# Mainboard_v1_1.net
KiCad netlist of a schematic drawn in Altium Designer
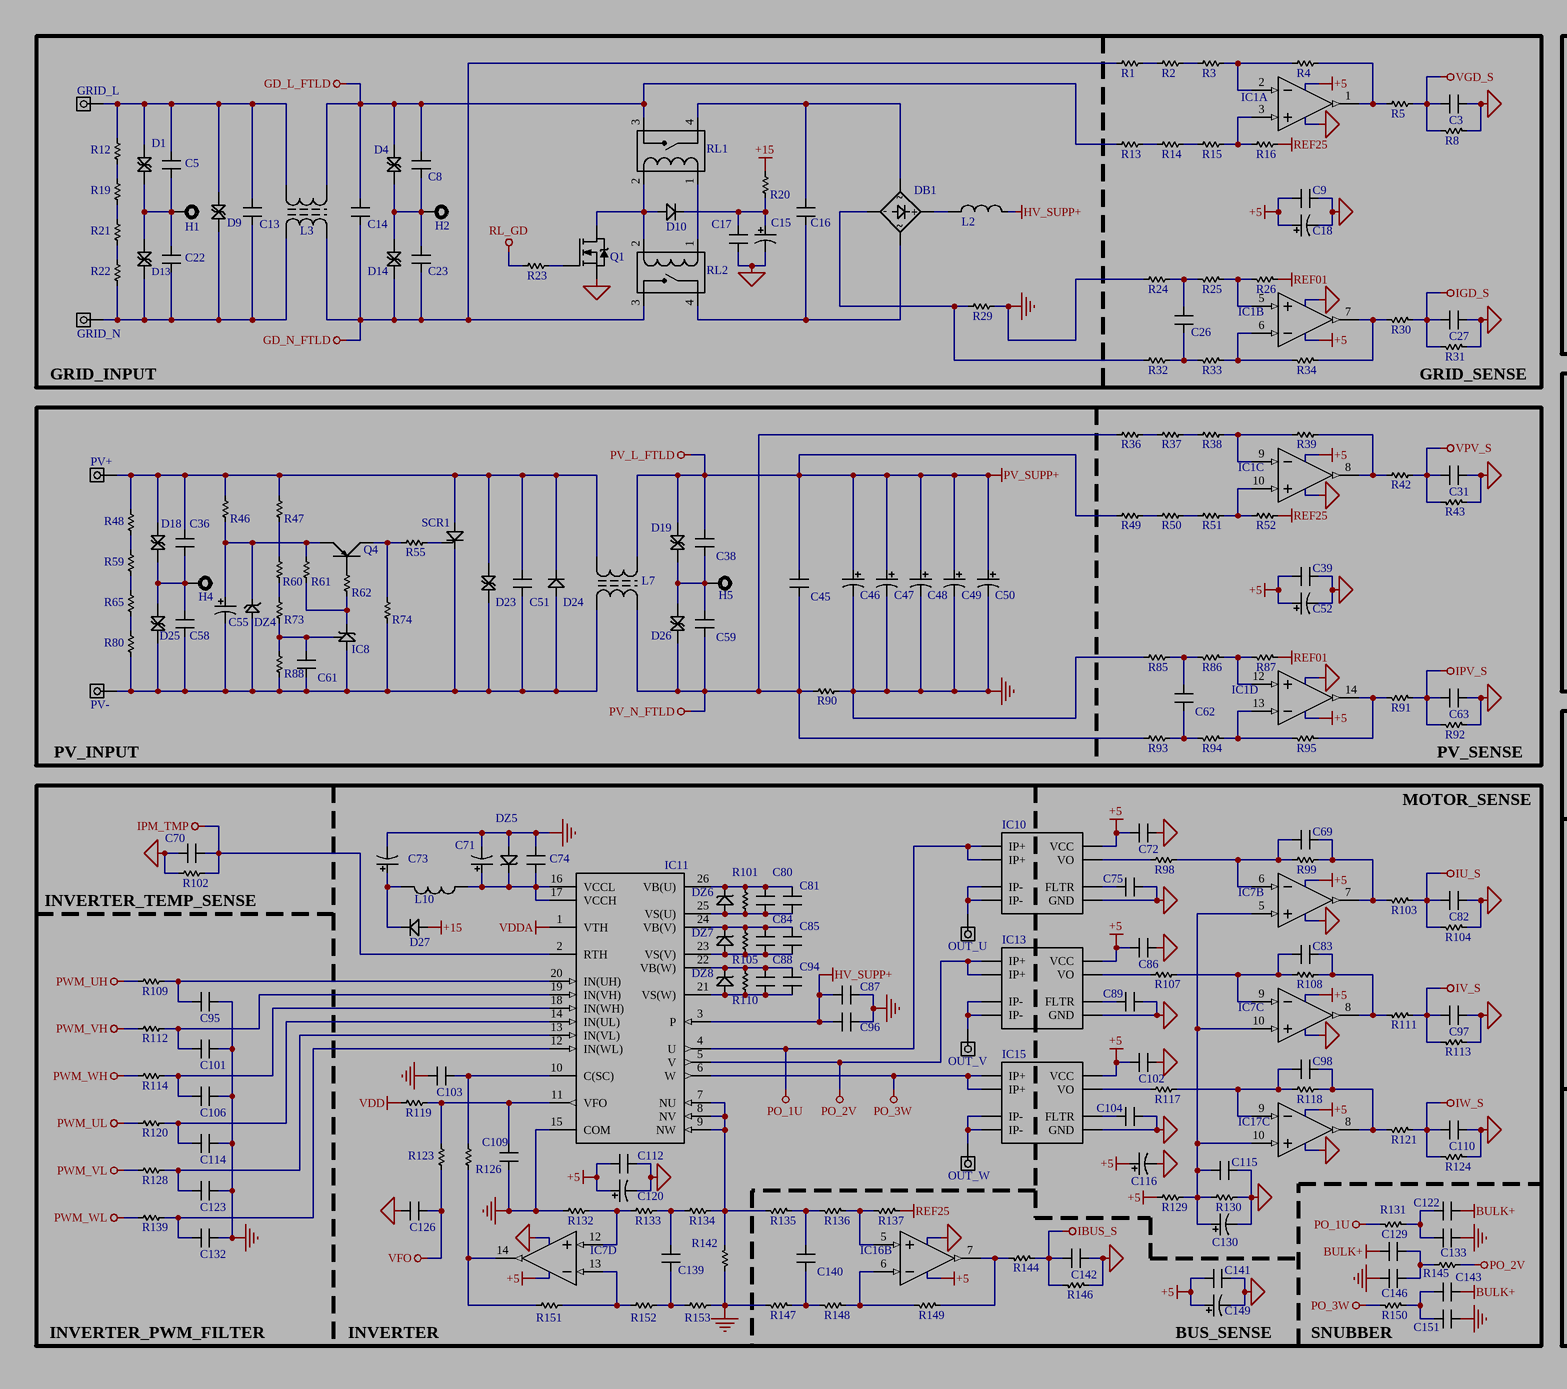
[diagram p0: Mainboard_v1_1.SchDoc, left]
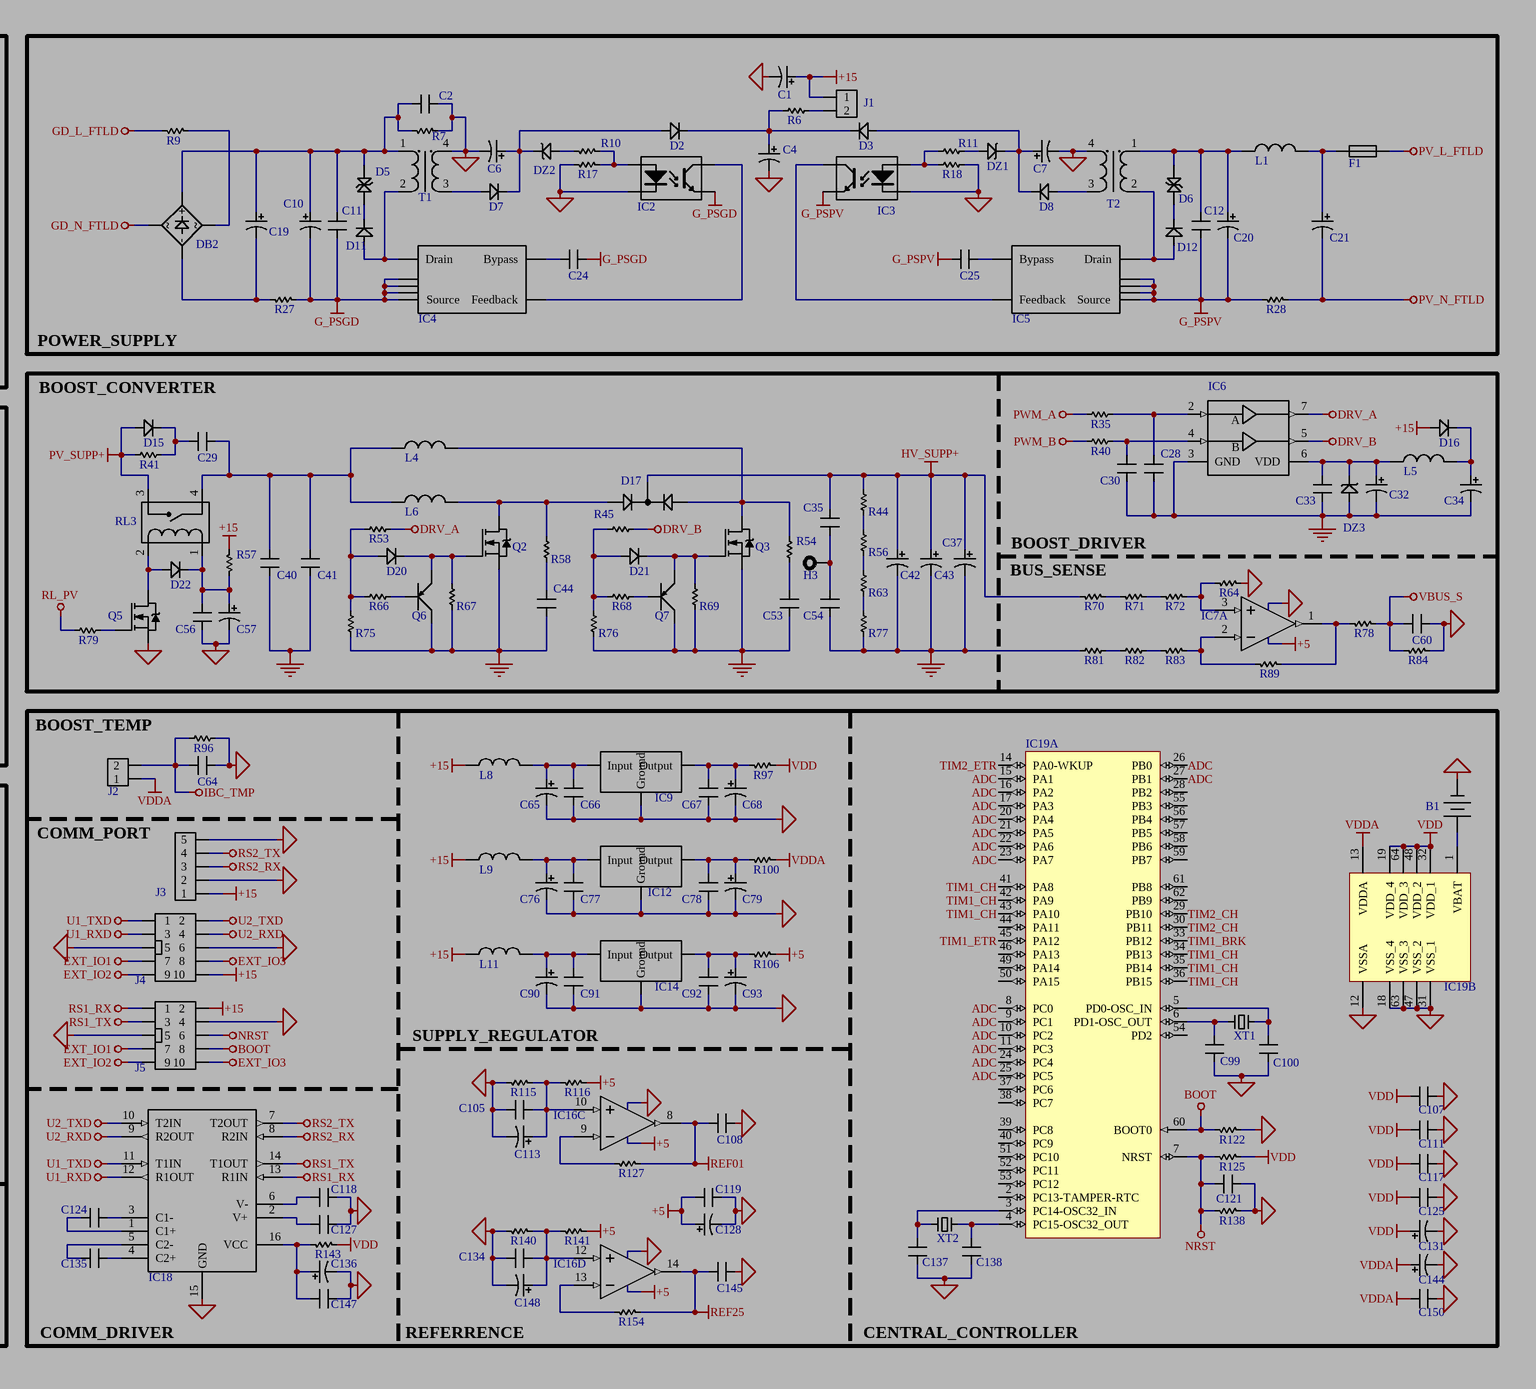
[diagram p1: Mainboard_v1_1.SchDoc, right]

(export (version "E")
  (design (tool "Eeschema 10.0.6"))
  (components
    (comp (ref "B1") (value "BATTERY") (libsource (lib "MeoLib_v2") (part "BATTERY")))
    (comp (ref "C1") (value "CAP-POL") (footprint "CAP-ELECT-5") (libsource (lib "") (part "CAP-POL_1")))
    (comp (ref "C2") (value "104") (footprint "CAP20") (libsource (lib "MeoLib_v2") (part "CAP")))
    (comp (ref "C3") (value "104") (footprint "CAP20") (libsource (lib "MeoLib_v2") (part "CAP")))
    (comp (ref "C4") (value "CAP-POL") (footprint "CAP-ELECT-5") (libsource (lib "") (part "CAP-POL_1")))
    (comp (ref "C5") (value "104") (footprint "CAP20") (libsource (lib "MeoLib_v2") (part "CAP")))
    (comp (ref "C6") (value "CAP-POL") (footprint "CAP-ELECT-5") (libsource (lib "") (part "CAP-POL_1")))
    (comp (ref "C7")
      (value "CAP-POL")
      (footprint "CAP-ELECT-5")
      (libsource (lib "MeoLib_v2") (part "CAP-POL"))
    )
    (comp (ref "C8") (value "104") (footprint "CAP20") (libsource (lib "MeoLib_v2") (part "CAP")))
    (comp (ref "C9") (value "104") (footprint "CAP20") (libsource (lib "MeoLib_v2") (part "CAP")))
    (comp (ref "C10")
      (value "CAP-POL")
      (footprint "CAP-ELECT-5")
      (libsource (lib "MeoLib_v2") (part "CAP-POL"))
    )
    (comp (ref "C11") (value "104") (footprint "CAP20") (libsource (lib "MeoLib_v2") (part "CAP")))
    (comp (ref "C12") (value "104") (footprint "CAP20") (libsource (lib "MeoLib_v2") (part "CAP")))
    (comp (ref "C13") (value "104") (footprint "CAP20") (libsource (lib "MeoLib_v2") (part "CAP")))
    (comp (ref "C14") (value "104") (footprint "CAP20") (libsource (lib "MeoLib_v2") (part "CAP")))
    (comp (ref "C15")
      (value "CAP-POL")
      (footprint "CAP-ELECT-5")
      (libsource (lib "MeoLib_v2") (part "CAP-POL"))
    )
    (comp (ref "C16") (value "NULL") (footprint "CAP20") (libsource (lib "MeoLib_v2") (part "CAP")))
    (comp (ref "C17") (value "CAP") (footprint "CAP20") (libsource (lib "MeoLib_v2") (part "CAP")))
    (comp (ref "C18")
      (value "CAP-POL")
      (footprint "CAP-ELECT-5")
      (libsource (lib "MeoLib_v2") (part "CAP-POL"))
    )
    (comp (ref "C19") (value "CAP-POL") (footprint "CAP-ELECT-5") (libsource (lib "") (part "CAP-POL_1")))
    (comp (ref "C20") (value "CAP-POL") (footprint "CAP-ELECT-5") (libsource (lib "") (part "CAP-POL_1")))
    (comp (ref "C21") (value "CAP-POL") (footprint "CAP-ELECT-5") (libsource (lib "") (part "CAP-POL_1")))
    (comp (ref "C22") (value "104") (footprint "CAP20") (libsource (lib "MeoLib_v2") (part "CAP")))
    (comp (ref "C23") (value "104") (footprint "CAP20") (libsource (lib "MeoLib_v2") (part "CAP")))
    (comp (ref "C24") (value "104") (footprint "CAP20") (libsource (lib "MeoLib_v2") (part "CAP")))
    (comp (ref "C25") (value "104") (footprint "CAP20") (libsource (lib "MeoLib_v2") (part "CAP")))
    (comp (ref "C26") (value "104") (footprint "CAP20") (libsource (lib "MeoLib_v2") (part "CAP")))
    (comp (ref "C27") (value "104") (footprint "CAP20") (libsource (lib "MeoLib_v2") (part "CAP")))
    (comp (ref "C28") (value "104") (footprint "CAP20") (libsource (lib "MeoLib_v2") (part "CAP")))
    (comp (ref "C29") (value "104") (footprint "CAP20") (libsource (lib "MeoLib_v2") (part "CAP")))
    (comp (ref "C30") (value "104") (footprint "CAP20") (libsource (lib "MeoLib_v2") (part "CAP")))
    (comp (ref "C31") (value "104") (footprint "CAP20") (libsource (lib "MeoLib_v2") (part "CAP")))
    (comp (ref "C32") (value "CAP-POL") (footprint "CAP-ELECT-5") (libsource (lib "") (part "CAP-POL_1")))
    (comp (ref "C33") (value "104") (footprint "CAP20") (libsource (lib "MeoLib_v2") (part "CAP")))
    (comp (ref "C34") (value "CAP-POL") (footprint "CAP-ELECT-5") (libsource (lib "") (part "CAP-POL_1")))
    (comp (ref "C35") (value "104") (footprint "CAP20") (libsource (lib "MeoLib_v2") (part "CAP")))
    (comp (ref "C36") (value "104") (footprint "CAP20") (libsource (lib "MeoLib_v2") (part "CAP")))
    (comp (ref "C37") (value "CAP-POL") (footprint "CAP-ELECT-5") (libsource (lib "") (part "CAP-POL_1")))
    (comp (ref "C38") (value "104") (footprint "CAP20") (libsource (lib "MeoLib_v2") (part "CAP")))
    (comp (ref "C39") (value "104") (footprint "CAP20") (libsource (lib "MeoLib_v2") (part "CAP")))
    (comp (ref "C40") (value "104") (footprint "CAP20") (libsource (lib "MeoLib_v2") (part "CAP")))
    (comp (ref "C41") (value "104") (footprint "CAP20") (libsource (lib "MeoLib_v2") (part "CAP")))
    (comp (ref "C42") (value "CAP-POL") (footprint "CAP-ELECT-5") (libsource (lib "") (part "CAP-POL_1")))
    (comp (ref "C43") (value "CAP-POL") (footprint "CAP-ELECT-5") (libsource (lib "") (part "CAP-POL_1")))
    (comp (ref "C44") (value "104") (footprint "CAP20") (libsource (lib "MeoLib_v2") (part "CAP")))
    (comp (ref "C45") (value "104") (footprint "CAP20") (libsource (lib "MeoLib_v2") (part "CAP")))
    (comp (ref "C46") (value "CAP-POL") (footprint "CAP-ELECT-5") (libsource (lib "") (part "CAP-POL_1")))
    (comp (ref "C47") (value "CAP-POL") (footprint "CAP-ELECT-5") (libsource (lib "") (part "CAP-POL_1")))
    (comp (ref "C48") (value "CAP-POL") (footprint "CAP-ELECT-5") (libsource (lib "") (part "CAP-POL_1")))
    (comp (ref "C49") (value "CAP-POL") (footprint "CAP-ELECT-5") (libsource (lib "") (part "CAP-POL_1")))
    (comp (ref "C50") (value "CAP-POL") (footprint "CAP-ELECT-5") (libsource (lib "") (part "CAP-POL_1")))
    (comp (ref "C51") (value "104") (footprint "CAP20") (libsource (lib "MeoLib_v2") (part "CAP")))
    (comp (ref "C52")
      (value "CAP-POL")
      (footprint "CAP-ELECT-5")
      (libsource (lib "MeoLib_v2") (part "CAP-POL"))
    )
    (comp (ref "C53") (value "104") (footprint "CAP20") (libsource (lib "MeoLib_v2") (part "CAP")))
    (comp (ref "C54") (value "104") (footprint "CAP20") (libsource (lib "MeoLib_v2") (part "CAP")))
    (comp (ref "C55")
      (value "CAP-POL")
      (footprint "CAP-ELECT-5")
      (libsource (lib "MeoLib_v2") (part "CAP-POL"))
    )
    (comp (ref "C56") (value "104") (footprint "CAP20") (libsource (lib "MeoLib_v2") (part "CAP")))
    (comp (ref "C57") (value "CAP-POL") (footprint "CAP-ELECT-5") (libsource (lib "") (part "CAP-POL_1")))
    (comp (ref "C58") (value "104") (footprint "CAP20") (libsource (lib "MeoLib_v2") (part "CAP")))
    (comp (ref "C59") (value "104") (footprint "CAP20") (libsource (lib "MeoLib_v2") (part "CAP")))
    (comp (ref "C60") (value "104") (footprint "CAP20") (libsource (lib "MeoLib_v2") (part "CAP")))
    (comp (ref "C61") (value "104") (footprint "CAP20") (libsource (lib "MeoLib_v2") (part "CAP")))
    (comp (ref "C62") (value "104") (footprint "CAP20") (libsource (lib "MeoLib_v2") (part "CAP")))
    (comp (ref "C63") (value "104") (footprint "CAP20") (libsource (lib "MeoLib_v2") (part "CAP")))
    (comp (ref "C64") (value "104") (footprint "CAP20") (libsource (lib "MeoLib_v2") (part "CAP")))
    (comp (ref "C65") (value "CAP-POL") (footprint "CAP-ELECT-5") (libsource (lib "") (part "CAP-POL_1")))
    (comp (ref "C66") (value "CAP") (footprint "CAP20") (libsource (lib "MeoLib_v2") (part "CAP")))
    (comp (ref "C67") (value "CAP") (footprint "CAP20") (libsource (lib "MeoLib_v2") (part "CAP")))
    (comp (ref "C68")
      (value "CAP-POL")
      (footprint "CAP-ELECT-5")
      (libsource (lib "MeoLib_v2") (part "CAP-POL"))
    )
    (comp (ref "C69") (value "104") (footprint "CAP20") (libsource (lib "MeoLib_v2") (part "CAP")))
    (comp (ref "C70") (value "104") (footprint "CAP20") (libsource (lib "MeoLib_v2") (part "CAP")))
    (comp (ref "C71") (value "CAP-POL") (footprint "CAP-ELECT-5") (libsource (lib "") (part "CAP-POL_1")))
    (comp (ref "C72") (value "104") (footprint "CAP20") (libsource (lib "MeoLib_v2") (part "CAP")))
    (comp (ref "C73") (value "CAP-POL") (footprint "CAP-ELECT-5") (libsource (lib "") (part "CAP-POL_1")))
    (comp (ref "C74") (value "104") (footprint "CAP20") (libsource (lib "MeoLib_v2") (part "CAP")))
    (comp (ref "C75") (value "104") (footprint "CAP20") (libsource (lib "MeoLib_v2") (part "CAP")))
    (comp (ref "C76") (value "CAP-POL") (footprint "CAP-ELECT-5") (libsource (lib "") (part "CAP-POL_1")))
    (comp (ref "C77") (value "CAP") (footprint "CAP20") (libsource (lib "MeoLib_v2") (part "CAP")))
    (comp (ref "C78") (value "CAP") (footprint "CAP20") (libsource (lib "MeoLib_v2") (part "CAP")))
    (comp (ref "C79")
      (value "CAP-POL")
      (footprint "CAP-ELECT-5")
      (libsource (lib "MeoLib_v2") (part "CAP-POL"))
    )
    (comp (ref "C80") (value "104") (footprint "CAP20") (libsource (lib "MeoLib_v2") (part "CAP")))
    (comp (ref "C81") (value "104") (footprint "CAP20") (libsource (lib "MeoLib_v2") (part "CAP")))
    (comp (ref "C82") (value "104") (footprint "CAP20") (libsource (lib "MeoLib_v2") (part "CAP")))
    (comp (ref "C83") (value "104") (footprint "CAP20") (libsource (lib "MeoLib_v2") (part "CAP")))
    (comp (ref "C84") (value "104") (footprint "CAP20") (libsource (lib "MeoLib_v2") (part "CAP")))
    (comp (ref "C85") (value "104") (footprint "CAP20") (libsource (lib "MeoLib_v2") (part "CAP")))
    (comp (ref "C86") (value "104") (footprint "CAP20") (libsource (lib "MeoLib_v2") (part "CAP")))
    (comp (ref "C87") (value "104") (footprint "CAP20") (libsource (lib "MeoLib_v2") (part "CAP")))
    (comp (ref "C88") (value "104") (footprint "CAP20") (libsource (lib "MeoLib_v2") (part "CAP")))
    (comp (ref "C89") (value "104") (footprint "CAP20") (libsource (lib "MeoLib_v2") (part "CAP")))
    (comp (ref "C90") (value "CAP-POL") (footprint "CAP-ELECT-5") (libsource (lib "") (part "CAP-POL_1")))
    (comp (ref "C91") (value "CAP") (footprint "CAP20") (libsource (lib "MeoLib_v2") (part "CAP")))
    (comp (ref "C92") (value "CAP") (footprint "CAP20") (libsource (lib "MeoLib_v2") (part "CAP")))
    (comp (ref "C93")
      (value "CAP-POL")
      (footprint "CAP-ELECT-5")
      (libsource (lib "MeoLib_v2") (part "CAP-POL"))
    )
    (comp (ref "C94") (value "104") (footprint "CAP20") (libsource (lib "MeoLib_v2") (part "CAP")))
    (comp (ref "C95") (value "104") (footprint "CAP20") (libsource (lib "MeoLib_v2") (part "CAP")))
    (comp (ref "C96") (value "104") (footprint "CAP20") (libsource (lib "MeoLib_v2") (part "CAP")))
    (comp (ref "C97") (value "104") (footprint "CAP20") (libsource (lib "MeoLib_v2") (part "CAP")))
    (comp (ref "C98") (value "104") (footprint "CAP20") (libsource (lib "MeoLib_v2") (part "CAP")))
    (comp (ref "C99") (value "CAP") (footprint "CAP20") (libsource (lib "MeoLib_v2") (part "CAP")))
    (comp (ref "C100") (value "CAP") (footprint "CAP20") (libsource (lib "MeoLib_v2") (part "CAP")))
    (comp (ref "C101") (value "104") (footprint "CAP20") (libsource (lib "MeoLib_v2") (part "CAP")))
    (comp (ref "C102") (value "104") (footprint "CAP20") (libsource (lib "MeoLib_v2") (part "CAP")))
    (comp (ref "C103") (value "104") (footprint "CAP20") (libsource (lib "MeoLib_v2") (part "CAP")))
    (comp (ref "C104") (value "104") (footprint "CAP20") (libsource (lib "MeoLib_v2") (part "CAP")))
    (comp (ref "C105") (value "104") (footprint "CAP20") (libsource (lib "MeoLib_v2") (part "CAP")))
    (comp (ref "C106") (value "104") (footprint "CAP20") (libsource (lib "MeoLib_v2") (part "CAP")))
    (comp (ref "C107") (value "CAP") (footprint "CAP20") (libsource (lib "MeoLib_v2") (part "CAP")))
    (comp (ref "C108") (value "104") (footprint "CAP20") (libsource (lib "MeoLib_v2") (part "CAP")))
    (comp (ref "C109") (value "104") (footprint "CAP20") (libsource (lib "MeoLib_v2") (part "CAP")))
    (comp (ref "C110") (value "104") (footprint "CAP20") (libsource (lib "MeoLib_v2") (part "CAP")))
    (comp (ref "C111") (value "CAP") (footprint "CAP20") (libsource (lib "MeoLib_v2") (part "CAP")))
    (comp (ref "C112") (value "104") (footprint "CAP20") (libsource (lib "MeoLib_v2") (part "CAP")))
    (comp (ref "C113") (value "CAP-POL") (footprint "CAP-ELECT-5") (libsource (lib "") (part "CAP-POL_1")))
    (comp (ref "C114") (value "104") (footprint "CAP20") (libsource (lib "MeoLib_v2") (part "CAP")))
    (comp (ref "C115") (value "104") (footprint "CAP20") (libsource (lib "MeoLib_v2") (part "CAP")))
    (comp (ref "C116")
      (value "CAP-POL")
      (footprint "CAP-ELECT-5")
      (libsource (lib "MeoLib_v2") (part "CAP-POL"))
    )
    (comp (ref "C117") (value "CAP") (footprint "CAP20") (libsource (lib "MeoLib_v2") (part "CAP")))
    (comp (ref "C118") (value "CAP") (footprint "CAP20") (libsource (lib "MeoLib_v2") (part "CAP")))
    (comp (ref "C119") (value "104") (footprint "CAP20") (libsource (lib "MeoLib_v2") (part "CAP")))
    (comp (ref "C120")
      (value "CAP-POL")
      (footprint "CAP-ELECT-5")
      (libsource (lib "MeoLib_v2") (part "CAP-POL"))
    )
    (comp (ref "C121") (value "104") (footprint "CAP20") (libsource (lib "MeoLib_v2") (part "CAP")))
    (comp (ref "C122") (value "104") (footprint "CAP20") (libsource (lib "MeoLib_v2") (part "CAP")))
    (comp (ref "C123") (value "104") (footprint "CAP20") (libsource (lib "MeoLib_v2") (part "CAP")))
    (comp (ref "C124") (value "CAP") (footprint "CAP20") (libsource (lib "MeoLib_v2") (part "CAP")))
    (comp (ref "C125") (value "CAP") (footprint "CAP20") (libsource (lib "MeoLib_v2") (part "CAP")))
    (comp (ref "C126") (value "104") (footprint "CAP20") (libsource (lib "MeoLib_v2") (part "CAP")))
    (comp (ref "C127") (value "CAP") (footprint "CAP20") (libsource (lib "MeoLib_v2") (part "CAP")))
    (comp (ref "C128")
      (value "CAP-POL")
      (footprint "CAP-ELECT-5")
      (libsource (lib "MeoLib_v2") (part "CAP-POL"))
    )
    (comp (ref "C129") (value "104") (footprint "CAP20") (libsource (lib "MeoLib_v2") (part "CAP")))
    (comp (ref "C130")
      (value "CAP-POL")
      (footprint "CAP-ELECT-5")
      (libsource (lib "MeoLib_v2") (part "CAP-POL"))
    )
    (comp (ref "C131")
      (value "CAP-POL")
      (footprint "CAP-ELECT-5")
      (libsource (lib "MeoLib_v2") (part "CAP-POL"))
    )
    (comp (ref "C132") (value "104") (footprint "CAP20") (libsource (lib "MeoLib_v2") (part "CAP")))
    (comp (ref "C133") (value "104") (footprint "CAP20") (libsource (lib "MeoLib_v2") (part "CAP")))
    (comp (ref "C134") (value "104") (footprint "CAP20") (libsource (lib "MeoLib_v2") (part "CAP")))
    (comp (ref "C135") (value "CAP") (footprint "CAP20") (libsource (lib "MeoLib_v2") (part "CAP")))
    (comp (ref "C136")
      (value "CAP-POL")
      (footprint "CAP-ELECT-5")
      (libsource (lib "MeoLib_v2") (part "CAP-POL"))
    )
    (comp (ref "C137") (value "CAP") (footprint "CAP20") (libsource (lib "MeoLib_v2") (part "CAP")))
    (comp (ref "C138") (value "CAP") (footprint "CAP20") (libsource (lib "MeoLib_v2") (part "CAP")))
    (comp (ref "C139") (value "104") (footprint "CAP20") (libsource (lib "MeoLib_v2") (part "CAP")))
    (comp (ref "C140") (value "104") (footprint "CAP20") (libsource (lib "MeoLib_v2") (part "CAP")))
    (comp (ref "C141") (value "104") (footprint "CAP20") (libsource (lib "MeoLib_v2") (part "CAP")))
    (comp (ref "C142") (value "104") (footprint "CAP20") (libsource (lib "MeoLib_v2") (part "CAP")))
    (comp (ref "C143") (value "104") (footprint "CAP20") (libsource (lib "MeoLib_v2") (part "CAP")))
    (comp (ref "C144")
      (value "CAP-POL")
      (footprint "CAP-ELECT-5")
      (libsource (lib "MeoLib_v2") (part "CAP-POL"))
    )
    (comp (ref "C145") (value "104") (footprint "CAP20") (libsource (lib "MeoLib_v2") (part "CAP")))
    (comp (ref "C146") (value "104") (footprint "CAP20") (libsource (lib "MeoLib_v2") (part "CAP")))
    (comp (ref "C147") (value "CAP") (footprint "CAP20") (libsource (lib "MeoLib_v2") (part "CAP")))
    (comp (ref "C148") (value "CAP-POL") (footprint "CAP-ELECT-5") (libsource (lib "") (part "CAP-POL_1")))
    (comp (ref "C149")
      (value "CAP-POL")
      (footprint "CAP-ELECT-5")
      (libsource (lib "MeoLib_v2") (part "CAP-POL"))
    )
    (comp (ref "C150") (value "CAP") (footprint "CAP20") (libsource (lib "MeoLib_v2") (part "CAP")))
    (comp (ref "C151") (value "104") (footprint "CAP20") (libsource (lib "MeoLib_v2") (part "CAP")))
    (comp (ref "D1") (value "DB3") (footprint "DIA_DB3") (libsource (lib "MeoLib_v2") (part "DB3")))
    (comp (ref "D2")
      (value "Diode")
      (footprint "DIO_DO41")
      (fields (field (name "PUBLISHER") "Altium Limited"))
      (libsource (lib "MeoLib_v2") (part "Diode"))
    )
    (comp (ref "D3")
      (value "Diode")
      (footprint "DIO_DO41")
      (fields (field (name "PUBLISHER") "Altium Limited"))
      (libsource (lib "MeoLib_v2") (part "Diode"))
    )
    (comp (ref "D4") (value "DB3") (footprint "DIA_DB3") (libsource (lib "MeoLib_v2") (part "DB3")))
    (comp (ref "D5")
      (value "Diode TVS")
      (footprint "DIO_DO15-TVS")
      (libsource (lib "MeoLib_v2") (part "Diode TVS"))
    )
    (comp (ref "D6")
      (value "Diode TVS")
      (footprint "DIO_DO15-TVS")
      (libsource (lib "MeoLib_v2") (part "Diode TVS"))
    )
    (comp (ref "D7")
      (value "Diode")
      (footprint "DIO_DO41")
      (fields (field (name "PUBLISHER") "Altium Limited"))
      (libsource (lib "MeoLib_v2") (part "Diode"))
    )
    (comp (ref "D8")
      (value "Diode")
      (footprint "DIO_DO41")
      (fields (field (name "PUBLISHER") "Altium Limited"))
      (libsource (lib "MeoLib_v2") (part "Diode"))
    )
    (comp (ref "D9") (value "DB3") (footprint "DIA_DB3") (libsource (lib "MeoLib_v2") (part "DB3")))
    (comp (ref "D10")
      (value "Diode")
      (footprint "DIO_DO41")
      (fields (field (name "PUBLISHER") "Altium Limited"))
      (libsource (lib "MeoLib_v2") (part "Diode"))
    )
    (comp (ref "D11")
      (value "Diode")
      (footprint "DIO_DO41")
      (fields (field (name "PUBLISHER") "Altium Limited"))
      (libsource (lib "MeoLib_v2") (part "Diode"))
    )
    (comp (ref "D12")
      (value "Diode")
      (footprint "DIO_DO41")
      (fields (field (name "PUBLISHER") "Altium Limited"))
      (libsource (lib "MeoLib_v2") (part "Diode"))
    )
    (comp (ref "D13") (value "DB3") (footprint "DIA_DB3") (libsource (lib "MeoLib_v2") (part "DB3")))
    (comp (ref "D14") (value "DB3") (footprint "DIA_DB3") (libsource (lib "MeoLib_v2") (part "DB3")))
    (comp (ref "D15")
      (value "Diode")
      (footprint "DIO_DO41")
      (fields (field (name "PUBLISHER") "Altium Limited"))
      (libsource (lib "MeoLib_v2") (part "Diode"))
    )
    (comp (ref "D16")
      (value "Diode")
      (footprint "DIO_DO41")
      (fields (field (name "PUBLISHER") "Altium Limited"))
      (libsource (lib "MeoLib_v2") (part "Diode"))
    )
    (comp (ref "D17")
      (value "Diode Dual")
      (footprint "TO-220")
      (libsource (lib "MeoLib_v2") (part "Diode Dual"))
    )
    (comp (ref "D18") (value "DB3") (footprint "DIA_DB3") (libsource (lib "MeoLib_v2") (part "DB3")))
    (comp (ref "D19") (value "DB3") (footprint "DIA_DB3") (libsource (lib "MeoLib_v2") (part "DB3")))
    (comp (ref "D20")
      (value "Diode")
      (footprint "DIO_DO41")
      (fields (field (name "PUBLISHER") "Altium Limited"))
      (libsource (lib "MeoLib_v2") (part "Diode"))
    )
    (comp (ref "D21")
      (value "Diode")
      (footprint "DIO_DO41")
      (fields (field (name "PUBLISHER") "Altium Limited"))
      (libsource (lib "MeoLib_v2") (part "Diode"))
    )
    (comp (ref "D22")
      (value "Diode")
      (footprint "DIO_DO41")
      (fields (field (name "PUBLISHER") "Altium Limited"))
      (libsource (lib "MeoLib_v2") (part "Diode"))
    )
    (comp (ref "D23") (value "DB3") (footprint "DIA_DB3") (libsource (lib "MeoLib_v2") (part "DB3")))
    (comp (ref "D24")
      (value "Diode")
      (footprint "DIO_DO41")
      (fields (field (name "PUBLISHER") "Altium Limited"))
      (libsource (lib "MeoLib_v2") (part "Diode"))
    )
    (comp (ref "D25") (value "DB3") (footprint "DIA_DB3") (libsource (lib "MeoLib_v2") (part "DB3")))
    (comp (ref "D26") (value "DB3") (footprint "DIA_DB3") (libsource (lib "MeoLib_v2") (part "DB3")))
    (comp (ref "D27")
      (value "Diode")
      (footprint "DIO_DO41")
      (fields (field (name "PUBLISHER") "Altium Limited"))
      (libsource (lib "MeoLib_v2") (part "Diode"))
    )
    (comp (ref "DB1")
      (value "Diode Bridge")
      (footprint "DB25A")
      (libsource (lib "MeoLib_v2") (part "Diode Bridge"))
    )
    (comp (ref "DB2")
      (value "Diode Bridge")
      (footprint "DB25A")
      (libsource (lib "MeoLib_v2") (part "Diode Bridge"))
    )
    (comp (ref "DZ1")
      (value "Diode Zener")
      (footprint "DIO_DZ1W")
      (libsource (lib "MeoLib_v2") (part "Diode Zener"))
    )
    (comp (ref "DZ2")
      (value "Diode Zener")
      (footprint "DIO_DZ1W")
      (libsource (lib "MeoLib_v2") (part "Diode Zener"))
    )
    (comp (ref "DZ3")
      (value "Diode Zener")
      (footprint "DIO_DZ1W")
      (libsource (lib "MeoLib_v2") (part "Diode Zener"))
    )
    (comp (ref "DZ4")
      (value "Diode Zener")
      (footprint "DIO_DZ1W")
      (libsource (lib "") (part "Diode Zener_1"))
    )
    (comp (ref "DZ5")
      (value "Diode Zener")
      (footprint "DIO_DZ1W")
      (libsource (lib "MeoLib_v2") (part "Diode Zener"))
    )
    (comp (ref "DZ6")
      (value "Diode Zener")
      (footprint "DIO_DZ1W")
      (libsource (lib "MeoLib_v2") (part "Diode Zener"))
    )
    (comp (ref "DZ7")
      (value "Diode Zener")
      (footprint "DIO_DZ1W")
      (libsource (lib "MeoLib_v2") (part "Diode Zener"))
    )
    (comp (ref "DZ8")
      (value "Diode Zener")
      (footprint "DIO_DZ1W")
      (libsource (lib "MeoLib_v2") (part "Diode Zener"))
    )
    (comp (ref "F1") (value "Fuse") (footprint "F5x20") (libsource (lib "MeoLib_v2") (part "Fuse")))
    (comp (ref "H1") (value "HOLE") (footprint "HOLE_M3") (libsource (lib "MeoLib_v2") (part "HOLE")))
    (comp (ref "H2") (value "HOLE") (footprint "HOLE_M3") (libsource (lib "MeoLib_v2") (part "HOLE")))
    (comp (ref "H3") (value "HOLE") (footprint "HOLE_M3") (libsource (lib "MeoLib_v2") (part "HOLE")))
    (comp (ref "H4") (value "HOLE") (footprint "HOLE_M3") (libsource (lib "MeoLib_v2") (part "HOLE")))
    (comp (ref "H5") (value "HOLE") (footprint "HOLE_M3") (libsource (lib "MeoLib_v2") (part "HOLE")))
    (comp (ref "IC1")
      (value "MCP6024")
      (footprint "SO14")
      (fields (field (name "MANUFACTURER") "Microchip") (field (name "PARTNUMBER") "MCP6024-I/SL"))
      (libsource (lib "MeoLib_v2") (part "MCP6024"))
    )
    (comp (ref "IC2") (value "PC817") (footprint "DIP4") (libsource (lib "MeoLib_v2") (part "PC817")))
    (comp (ref "IC3") (value "PC817") (footprint "DIP4") (libsource (lib "MeoLib_v2") (part "PC817")))
    (comp (ref "IC4") (value "TNY27x") (footprint "DIP7-WO3") (libsource (lib "MeoLib_v2") (part "TNY27x")))
    (comp (ref "IC5") (value "TNY27x") (footprint "DIP7-WO3") (libsource (lib "") (part "TNY27x_1")))
    (comp (ref "IC6") (value "TC4424") (footprint "SO8") (libsource (lib "MeoLib_v2") (part "TC4424")))
    (comp (ref "IC7")
      (value "MCP6024")
      (footprint "SO14")
      (fields (field (name "MANUFACTURER") "Microchip") (field (name "PARTNUMBER") "MCP6024-I/SL"))
      (libsource (lib "MeoLib_v2") (part "MCP6024"))
    )
    (comp (ref "IC8") (value "TL431") (footprint "TO-92") (libsource (lib "MeoLib_v2") (part "TL431")))
    (comp (ref "IC9")
      (value "KA78xx")
      (footprint "TO-220")
      (description "Three Terminal Regulator")
      (libsource (lib "MeoLib_v2") (part "KA78xx"))
    )
    (comp (ref "IC10") (value "ACS712") (footprint "SO8") (libsource (lib "MeoLib_v2") (part "ACS712")))
    (comp (ref "IC11")
      (value "FNB41560")
      (footprint "FNB41560")
      (description "IGBT Array & Module Transistor, NPN, 15 A, 1.5 V, 32 W, 600 V, SPM26-AAA")
      (fields (field (name "MP") "FNB41060") (field (name "MF") "ON Semiconductor"))
      (libsource (lib "MeoLib_v2") (part "FNB41560"))
    )
    (comp (ref "IC12")
      (value "KA78xx")
      (footprint "TO-220")
      (description "Three Terminal Regulator")
      (libsource (lib "MeoLib_v2") (part "KA78xx"))
    )
    (comp (ref "IC13") (value "ACS712") (footprint "SO8") (libsource (lib "MeoLib_v2") (part "ACS712")))
    (comp (ref "IC14")
      (value "KA78xx")
      (footprint "TO-220")
      (description "Three Terminal Regulator")
      (libsource (lib "MeoLib_v2") (part "KA78xx"))
    )
    (comp (ref "IC15") (value "ACS712") (footprint "SO8") (libsource (lib "MeoLib_v2") (part "ACS712")))
    (comp (ref "IC16")
      (value "MCP6024")
      (footprint "SO14")
      (fields (field (name "MANUFACTURER") "Microchip") (field (name "PARTNUMBER") "MCP6024-I/SL"))
      (libsource (lib "MeoLib_v2") (part "MCP6024"))
    )
    (comp (ref "IC17")
      (value "MCP6024")
      (footprint "SO14")
      (fields (field (name "MANUFACTURER") "Microchip") (field (name "PARTNUMBER") "MCP6024-I/SL"))
      (libsource (lib "MeoLib_v2") (part "MCP6024"))
    )
    (comp (ref "IC18")
      (value "MAX3232")
      (fields
        (field (name "MANUFACTURER PART NUMBER") "MAX232DR")
        (field (name "MANUFACTURER") "Texas Instruments")
      )
      (libsource (lib "MeoLib_v2") (part "MAX3232"))
    )
    (comp (ref "IC19")
      (value "STM32F103RBT6")
      (footprint "STM-LQFP64_N")
      (libsource (lib "STMicroelectronics STM32 F1") (part "STM32F103RBT6"))
    )
    (comp (ref "J1")
      (value "Header2")
      (footprint "HDR2")
      (fields
        (field (name "MANUFACTURER") "Würth Elektronik eiSos GmbH")
        (field (name "PARTNO") "613002143121")
        (field (name "CREATED BY") "Karrer Zheng")
      )
      (libsource (lib "") (part "Header2_1"))
    )
    (comp (ref "J2")
      (value "Header2")
      (footprint "HDR2")
      (fields
        (field (name "MANUFACTURER") "Würth Elektronik eiSos GmbH")
        (field (name "PARTNO") "613002143121")
        (field (name "CREATED BY") "Karrer Zheng")
      )
      (libsource (lib "MeoLib_v2") (part "Header2"))
    )
    (comp (ref "J3") (value "Header5") (libsource (lib "MeoLib_v2") (part "Header5")))
    (comp (ref "J4") (value "Header5x2") (libsource (lib "MeoLib_v2") (part "Header5x2")))
    (comp (ref "J5") (value "Header5x2") (libsource (lib "MeoLib_v2") (part "Header5x2")))
    (comp (ref "L1")
      (value "Inductor")
      (footprint "IND_UPS3K")
      (libsource (lib "MeoLib_v2") (part "Inductor"))
    )
    (comp (ref "L2") (value "Inductor") (footprint "IND_UPS3K") (libsource (lib "") (part "Inductor_1")))
    (comp (ref "L3")
      (value "EMI_CHOKE")
      (footprint "IND_EMI")
      (libsource (lib "MeoLib_v2") (part "EMI_CHOKE"))
    )
    (comp (ref "L4")
      (value "Inductor")
      (footprint "IND_UPS3K")
      (libsource (lib "MeoLib_v2") (part "Inductor"))
    )
    (comp (ref "L5")
      (value "Inductor")
      (footprint "IND_UPS3K")
      (libsource (lib "MeoLib_v2") (part "Inductor"))
    )
    (comp (ref "L6")
      (value "Inductor")
      (footprint "IND_UPS3K")
      (libsource (lib "MeoLib_v2") (part "Inductor"))
    )
    (comp (ref "L7")
      (value "EMI_CHOKE")
      (footprint "IND_EMI")
      (libsource (lib "MeoLib_v2") (part "EMI_CHOKE"))
    )
    (comp (ref "L8")
      (value "Inductor")
      (footprint "IND_UPS3K")
      (libsource (lib "MeoLib_v2") (part "Inductor"))
    )
    (comp (ref "L9")
      (value "Inductor")
      (footprint "IND_UPS3K")
      (libsource (lib "MeoLib_v2") (part "Inductor"))
    )
    (comp (ref "L10")
      (value "Inductor")
      (footprint "IND_UPS3K")
      (libsource (lib "MeoLib_v2") (part "Inductor"))
    )
    (comp (ref "L11")
      (value "Inductor")
      (footprint "IND_UPS3K")
      (libsource (lib "MeoLib_v2") (part "Inductor"))
    )
    (comp (ref "Q1") (value "MOSFET_N") (footprint "TO-220") (libsource (lib "MeoLib_v2") (part "MOSFET_N")))
    (comp (ref "Q2") (value "MOSFET_N") (footprint "TO-220") (libsource (lib "MeoLib_v2") (part "MOSFET_N")))
    (comp (ref "Q3") (value "MOSFET_N") (footprint "TO-220") (libsource (lib "MeoLib_v2") (part "MOSFET_N")))
    (comp (ref "Q4") (value "BJT_PNP") (footprint "TO-92") (libsource (lib "MeoLib_v2") (part "BJT_PNP")))
    (comp (ref "Q5") (value "MOSFET_N") (footprint "TO-220") (libsource (lib "MeoLib_v2") (part "MOSFET_N")))
    (comp (ref "Q6") (value "BJT_PNP") (footprint "TO-92") (libsource (lib "MeoLib_v2") (part "BJT_PNP")))
    (comp (ref "Q7") (value "BJT_PNP") (footprint "TO-92") (libsource (lib "MeoLib_v2") (part "BJT_PNP")))
    (comp (ref "R1") (value "RES") (footprint "RES35") (libsource (lib "MeoLib_v2") (part "RES")))
    (comp (ref "R2") (value "RES") (footprint "RES35") (libsource (lib "MeoLib_v2") (part "RES")))
    (comp (ref "R3") (value "RES") (footprint "RES35") (libsource (lib "MeoLib_v2") (part "RES")))
    (comp (ref "R4") (value "RES") (footprint "RES35") (libsource (lib "MeoLib_v2") (part "RES")))
    (comp (ref "R5") (value "RES") (footprint "RES35") (libsource (lib "MeoLib_v2") (part "RES")))
    (comp (ref "R6") (value "RES") (footprint "RES35") (libsource (lib "MeoLib_v2") (part "RES")))
    (comp (ref "R7") (value "RES") (footprint "RES35") (libsource (lib "MeoLib_v2") (part "RES")))
    (comp (ref "R8") (value "RES") (footprint "RES35") (libsource (lib "MeoLib_v2") (part "RES")))
    (comp (ref "R9") (value "RES") (footprint "RES35") (libsource (lib "MeoLib_v2") (part "RES")))
    (comp (ref "R10") (value "RES") (footprint "RES35") (libsource (lib "MeoLib_v2") (part "RES")))
    (comp (ref "R11") (value "RES") (footprint "RES35") (libsource (lib "MeoLib_v2") (part "RES")))
    (comp (ref "R12") (value "RES") (footprint "RES35") (libsource (lib "MeoLib_v2") (part "RES")))
    (comp (ref "R13") (value "RES") (footprint "RES35") (libsource (lib "MeoLib_v2") (part "RES")))
    (comp (ref "R14") (value "RES") (footprint "RES35") (libsource (lib "MeoLib_v2") (part "RES")))
    (comp (ref "R15") (value "RES") (footprint "RES35") (libsource (lib "MeoLib_v2") (part "RES")))
    (comp (ref "R16") (value "RES") (footprint "RES35") (libsource (lib "MeoLib_v2") (part "RES")))
    (comp (ref "R17") (value "RES") (footprint "RES35") (libsource (lib "MeoLib_v2") (part "RES")))
    (comp (ref "R18") (value "RES") (footprint "RES35") (libsource (lib "MeoLib_v2") (part "RES")))
    (comp (ref "R19") (value "RES") (footprint "RES35") (libsource (lib "MeoLib_v2") (part "RES")))
    (comp (ref "R20") (value "RES") (footprint "RES35") (libsource (lib "MeoLib_v2") (part "RES")))
    (comp (ref "R21") (value "RES") (footprint "RES35") (libsource (lib "MeoLib_v2") (part "RES")))
    (comp (ref "R22") (value "RES") (footprint "RES35") (libsource (lib "MeoLib_v2") (part "RES")))
    (comp (ref "R23") (value "RES") (footprint "RES35") (libsource (lib "MeoLib_v2") (part "RES")))
    (comp (ref "R24") (value "RES") (footprint "RES35") (libsource (lib "MeoLib_v2") (part "RES")))
    (comp (ref "R25") (value "RES") (footprint "RES35") (libsource (lib "MeoLib_v2") (part "RES")))
    (comp (ref "R26") (value "RES") (footprint "RES35") (libsource (lib "MeoLib_v2") (part "RES")))
    (comp (ref "R27") (value "RES") (footprint "RES35") (libsource (lib "MeoLib_v2") (part "RES")))
    (comp (ref "R28") (value "RES") (footprint "RES35") (libsource (lib "MeoLib_v2") (part "RES")))
    (comp (ref "R29") (value "RES") (footprint "RES35") (libsource (lib "MeoLib_v2") (part "RES")))
    (comp (ref "R30") (value "RES") (footprint "RES35") (libsource (lib "MeoLib_v2") (part "RES")))
    (comp (ref "R31") (value "RES") (footprint "RES35") (libsource (lib "MeoLib_v2") (part "RES")))
    (comp (ref "R32") (value "RES") (footprint "RES35") (libsource (lib "MeoLib_v2") (part "RES")))
    (comp (ref "R33") (value "RES") (footprint "RES35") (libsource (lib "MeoLib_v2") (part "RES")))
    (comp (ref "R34") (value "RES") (footprint "RES35") (libsource (lib "MeoLib_v2") (part "RES")))
    (comp (ref "R35") (value "RES") (footprint "RES35") (libsource (lib "MeoLib_v2") (part "RES")))
    (comp (ref "R36") (value "RES") (footprint "RES35") (libsource (lib "MeoLib_v2") (part "RES")))
    (comp (ref "R37") (value "RES") (footprint "RES35") (libsource (lib "MeoLib_v2") (part "RES")))
    (comp (ref "R38") (value "RES") (footprint "RES35") (libsource (lib "MeoLib_v2") (part "RES")))
    (comp (ref "R39") (value "RES") (footprint "RES35") (libsource (lib "MeoLib_v2") (part "RES")))
    (comp (ref "R40") (value "RES") (footprint "RES35") (libsource (lib "MeoLib_v2") (part "RES")))
    (comp (ref "R41") (value "RES") (footprint "RES35") (libsource (lib "MeoLib_v2") (part "RES")))
    (comp (ref "R42") (value "RES") (footprint "RES35") (libsource (lib "MeoLib_v2") (part "RES")))
    (comp (ref "R43") (value "RES") (footprint "RES35") (libsource (lib "MeoLib_v2") (part "RES")))
    (comp (ref "R44") (value "RES") (footprint "RES35") (libsource (lib "MeoLib_v2") (part "RES")))
    (comp (ref "R45") (value "RES") (footprint "RES35") (libsource (lib "MeoLib_v2") (part "RES")))
    (comp (ref "R46") (value "RES") (footprint "RES35") (libsource (lib "MeoLib_v2") (part "RES")))
    (comp (ref "R47") (value "RES") (footprint "RES35") (libsource (lib "MeoLib_v2") (part "RES")))
    (comp (ref "R48") (value "RES") (footprint "RES35") (libsource (lib "MeoLib_v2") (part "RES")))
    (comp (ref "R49") (value "RES") (footprint "RES35") (libsource (lib "MeoLib_v2") (part "RES")))
    (comp (ref "R50") (value "RES") (footprint "RES35") (libsource (lib "MeoLib_v2") (part "RES")))
    (comp (ref "R51") (value "RES") (footprint "RES35") (libsource (lib "MeoLib_v2") (part "RES")))
    (comp (ref "R52") (value "RES") (footprint "RES35") (libsource (lib "MeoLib_v2") (part "RES")))
    (comp (ref "R53") (value "RES") (footprint "RES35") (libsource (lib "MeoLib_v2") (part "RES")))
    (comp (ref "R54") (value "RES") (footprint "RES35") (libsource (lib "MeoLib_v2") (part "RES")))
    (comp (ref "R55") (value "RES") (footprint "RES35") (libsource (lib "MeoLib_v2") (part "RES")))
    (comp (ref "R56") (value "RES") (footprint "RES35") (libsource (lib "MeoLib_v2") (part "RES")))
    (comp (ref "R57") (value "RES") (footprint "RES35") (libsource (lib "MeoLib_v2") (part "RES")))
    (comp (ref "R58") (value "RES") (footprint "RES35") (libsource (lib "MeoLib_v2") (part "RES")))
    (comp (ref "R59") (value "RES") (footprint "RES35") (libsource (lib "MeoLib_v2") (part "RES")))
    (comp (ref "R60") (value "RES") (footprint "RES35") (libsource (lib "MeoLib_v2") (part "RES")))
    (comp (ref "R61") (value "RES") (footprint "RES35") (libsource (lib "MeoLib_v2") (part "RES")))
    (comp (ref "R62") (value "RES") (footprint "RES35") (libsource (lib "MeoLib_v2") (part "RES")))
    (comp (ref "R63") (value "RES") (footprint "RES35") (libsource (lib "MeoLib_v2") (part "RES")))
    (comp (ref "R64") (value "RES") (footprint "RES35") (libsource (lib "MeoLib_v2") (part "RES")))
    (comp (ref "R65") (value "RES") (footprint "RES35") (libsource (lib "MeoLib_v2") (part "RES")))
    (comp (ref "R66") (value "RES") (footprint "RES35") (libsource (lib "MeoLib_v2") (part "RES")))
    (comp (ref "R67") (value "RES") (footprint "RES35") (libsource (lib "MeoLib_v2") (part "RES")))
    (comp (ref "R68") (value "RES") (footprint "RES35") (libsource (lib "MeoLib_v2") (part "RES")))
    (comp (ref "R69") (value "RES") (footprint "RES35") (libsource (lib "MeoLib_v2") (part "RES")))
    (comp (ref "R70") (value "RES") (footprint "RES35") (libsource (lib "MeoLib_v2") (part "RES")))
    (comp (ref "R71") (value "RES") (footprint "RES35") (libsource (lib "MeoLib_v2") (part "RES")))
    (comp (ref "R72") (value "RES") (footprint "RES35") (libsource (lib "MeoLib_v2") (part "RES")))
    (comp (ref "R73") (value "RES") (footprint "RES35") (libsource (lib "MeoLib_v2") (part "RES")))
    (comp (ref "R74") (value "RES") (footprint "RES35") (libsource (lib "MeoLib_v2") (part "RES")))
    (comp (ref "R75") (value "RES") (footprint "RES35") (libsource (lib "MeoLib_v2") (part "RES")))
    (comp (ref "R76") (value "RES") (footprint "RES35") (libsource (lib "MeoLib_v2") (part "RES")))
    (comp (ref "R77") (value "RES") (footprint "RES35") (libsource (lib "MeoLib_v2") (part "RES")))
    (comp (ref "R78") (value "RES") (footprint "RES35") (libsource (lib "MeoLib_v2") (part "RES")))
    (comp (ref "R79") (value "RES") (footprint "RES35") (libsource (lib "MeoLib_v2") (part "RES")))
    (comp (ref "R80") (value "RES") (footprint "RES35") (libsource (lib "MeoLib_v2") (part "RES")))
    (comp (ref "R81") (value "RES") (footprint "RES35") (libsource (lib "MeoLib_v2") (part "RES")))
    (comp (ref "R82") (value "RES") (footprint "RES35") (libsource (lib "MeoLib_v2") (part "RES")))
    (comp (ref "R83") (value "RES") (footprint "RES35") (libsource (lib "MeoLib_v2") (part "RES")))
    (comp (ref "R84") (value "RES") (footprint "RES35") (libsource (lib "MeoLib_v2") (part "RES")))
    (comp (ref "R85") (value "RES") (footprint "RES35") (libsource (lib "MeoLib_v2") (part "RES")))
    (comp (ref "R86") (value "RES") (footprint "RES35") (libsource (lib "MeoLib_v2") (part "RES")))
    (comp (ref "R87") (value "RES") (footprint "RES35") (libsource (lib "MeoLib_v2") (part "RES")))
    (comp (ref "R88") (value "RES") (footprint "RES35") (libsource (lib "MeoLib_v2") (part "RES")))
    (comp (ref "R89") (value "RES") (footprint "RES35") (libsource (lib "MeoLib_v2") (part "RES")))
    (comp (ref "R90") (value "RES") (footprint "RES35") (libsource (lib "MeoLib_v2") (part "RES")))
    (comp (ref "R91") (value "RES") (footprint "RES35") (libsource (lib "MeoLib_v2") (part "RES")))
    (comp (ref "R92") (value "RES") (footprint "RES35") (libsource (lib "MeoLib_v2") (part "RES")))
    (comp (ref "R93") (value "RES") (footprint "RES35") (libsource (lib "MeoLib_v2") (part "RES")))
    (comp (ref "R94") (value "RES") (footprint "RES35") (libsource (lib "MeoLib_v2") (part "RES")))
    (comp (ref "R95") (value "RES") (footprint "RES35") (libsource (lib "MeoLib_v2") (part "RES")))
    (comp (ref "R96") (value "RES") (footprint "RES35") (libsource (lib "MeoLib_v2") (part "RES")))
    (comp (ref "R97") (value "0") (footprint "RES35") (libsource (lib "MeoLib_v2") (part "RES")))
    (comp (ref "R98") (value "Ri") (footprint "RES35") (libsource (lib "MeoLib_v2") (part "RES")))
    (comp (ref "R99") (value "Rf") (footprint "RES35") (libsource (lib "MeoLib_v2") (part "RES")))
    (comp (ref "R100") (value "0") (footprint "RES35") (libsource (lib "MeoLib_v2") (part "RES")))
    (comp (ref "R101") (value "RES") (footprint "RES35") (libsource (lib "MeoLib_v2") (part "RES")))
    (comp (ref "R102") (value "RES") (footprint "RES35") (libsource (lib "MeoLib_v2") (part "RES")))
    (comp (ref "R103") (value "RES") (footprint "RES35") (libsource (lib "MeoLib_v2") (part "RES")))
    (comp (ref "R104") (value "RES") (footprint "RES35") (libsource (lib "MeoLib_v2") (part "RES")))
    (comp (ref "R105") (value "RES") (footprint "RES35") (libsource (lib "MeoLib_v2") (part "RES")))
    (comp (ref "R106") (value "0") (footprint "RES35") (libsource (lib "MeoLib_v2") (part "RES")))
    (comp (ref "R107") (value "Ri") (footprint "RES35") (libsource (lib "MeoLib_v2") (part "RES")))
    (comp (ref "R108") (value "Rf") (footprint "RES35") (libsource (lib "MeoLib_v2") (part "RES")))
    (comp (ref "R109") (value "RES") (footprint "RES35") (libsource (lib "MeoLib_v2") (part "RES")))
    (comp (ref "R110") (value "RES") (footprint "RES35") (libsource (lib "MeoLib_v2") (part "RES")))
    (comp (ref "R111") (value "RES") (footprint "RES35") (libsource (lib "MeoLib_v2") (part "RES")))
    (comp (ref "R112") (value "RES") (footprint "RES35") (libsource (lib "MeoLib_v2") (part "RES")))
    (comp (ref "R113") (value "RES") (footprint "RES35") (libsource (lib "MeoLib_v2") (part "RES")))
    (comp (ref "R114") (value "RES") (footprint "RES35") (libsource (lib "MeoLib_v2") (part "RES")))
    (comp (ref "R115") (value "RES") (footprint "RES35") (libsource (lib "MeoLib_v2") (part "RES")))
    (comp (ref "R116") (value "RES") (footprint "RES35") (libsource (lib "MeoLib_v2") (part "RES")))
    (comp (ref "R117") (value "Ri") (footprint "RES35") (libsource (lib "MeoLib_v2") (part "RES")))
    (comp (ref "R118") (value "Rf") (footprint "RES35") (libsource (lib "MeoLib_v2") (part "RES")))
    (comp (ref "R119") (value "RES") (footprint "RES35") (libsource (lib "MeoLib_v2") (part "RES")))
    (comp (ref "R120") (value "RES") (footprint "RES35") (libsource (lib "MeoLib_v2") (part "RES")))
    (comp (ref "R121") (value "RES") (footprint "RES35") (libsource (lib "MeoLib_v2") (part "RES")))
    (comp (ref "R122") (value "2K2") (footprint "RES40") (libsource (lib "MeoLib_v2") (part "RES")))
    (comp (ref "R123") (value "RES") (footprint "RES35") (libsource (lib "MeoLib_v2") (part "RES")))
    (comp (ref "R124") (value "RES") (footprint "RES35") (libsource (lib "MeoLib_v2") (part "RES")))
    (comp (ref "R125") (value "2K2") (footprint "RES40") (libsource (lib "MeoLib_v2") (part "RES")))
    (comp (ref "R126") (value "RES") (footprint "RES35") (libsource (lib "MeoLib_v2") (part "RES")))
    (comp (ref "R127") (value "RES") (footprint "RES35") (libsource (lib "MeoLib_v2") (part "RES")))
    (comp (ref "R128") (value "RES") (footprint "RES35") (libsource (lib "MeoLib_v2") (part "RES")))
    (comp (ref "R129") (value "RES") (footprint "RES35") (libsource (lib "MeoLib_v2") (part "RES")))
    (comp (ref "R130") (value "RES") (footprint "RES35") (libsource (lib "MeoLib_v2") (part "RES")))
    (comp (ref "R131") (value "RES") (footprint "RES35") (libsource (lib "MeoLib_v2") (part "RES")))
    (comp (ref "R132") (value "RES") (footprint "RES35") (libsource (lib "MeoLib_v2") (part "RES")))
    (comp (ref "R133") (value "RES") (footprint "RES35") (libsource (lib "MeoLib_v2") (part "RES")))
    (comp (ref "R134") (value "RES") (footprint "RES35") (libsource (lib "MeoLib_v2") (part "RES")))
    (comp (ref "R135") (value "RES") (footprint "RES35") (libsource (lib "MeoLib_v2") (part "RES")))
    (comp (ref "R136") (value "RES") (footprint "RES35") (libsource (lib "MeoLib_v2") (part "RES")))
    (comp (ref "R137") (value "RES") (footprint "RES35") (libsource (lib "MeoLib_v2") (part "RES")))
    (comp (ref "R138") (value "2K2") (footprint "RES40") (libsource (lib "MeoLib_v2") (part "RES")))
    (comp (ref "R139") (value "RES") (footprint "RES35") (libsource (lib "MeoLib_v2") (part "RES")))
    (comp (ref "R140") (value "RES") (footprint "RES35") (libsource (lib "MeoLib_v2") (part "RES")))
    (comp (ref "R141") (value "RES") (footprint "RES35") (libsource (lib "MeoLib_v2") (part "RES")))
    (comp (ref "R142") (value "RES") (footprint "RES35") (libsource (lib "MeoLib_v2") (part "RES")))
    (comp (ref "R143") (value "0") (footprint "RES35") (libsource (lib "MeoLib_v2") (part "RES")))
    (comp (ref "R144") (value "RES") (footprint "RES35") (libsource (lib "MeoLib_v2") (part "RES")))
    (comp (ref "R145") (value "RES") (footprint "RES35") (libsource (lib "MeoLib_v2") (part "RES")))
    (comp (ref "R146") (value "RES") (footprint "RES35") (libsource (lib "MeoLib_v2") (part "RES")))
    (comp (ref "R147") (value "RES") (footprint "RES35") (libsource (lib "MeoLib_v2") (part "RES")))
    (comp (ref "R148") (value "RES") (footprint "RES35") (libsource (lib "MeoLib_v2") (part "RES")))
    (comp (ref "R149") (value "RES") (footprint "RES35") (libsource (lib "MeoLib_v2") (part "RES")))
    (comp (ref "R150") (value "RES") (footprint "RES35") (libsource (lib "MeoLib_v2") (part "RES")))
    (comp (ref "R151") (value "RES") (footprint "RES35") (libsource (lib "MeoLib_v2") (part "RES")))
    (comp (ref "R152") (value "RES") (footprint "RES35") (libsource (lib "MeoLib_v2") (part "RES")))
    (comp (ref "R153") (value "RES") (footprint "RES35") (libsource (lib "MeoLib_v2") (part "RES")))
    (comp (ref "R154") (value "RES") (footprint "RES35") (libsource (lib "MeoLib_v2") (part "RES")))
    (comp (ref "RL1") (value "RELAY SPST") (libsource (lib "") (part "RELAY SPST_1")))
    (comp (ref "RL2") (value "RELAY SPST") (libsource (lib "MeoLib_v2") (part "RELAY SPST")))
    (comp (ref "RL3") (value "RELAY SPST") (libsource (lib "") (part "RELAY SPST_1")))
    (comp (ref "SCR1") (value "SCR") (footprint "TO-220") (libsource (lib "MeoLib_v2") (part "SCR")))
    (comp (ref "T1")
      (value "PT_FLYBACK_2IN-2OUT")
      (footprint "E16_DRV")
      (description "2 input 2 output flyback potential transformer")
      (libsource (lib "MeoLib_v2") (part "PT_FLYBACK_2IN-2OUT"))
    )
    (comp (ref "T2")
      (value "PT_FLYBACK_2IN-2OUT")
      (footprint "E16_DRV")
      (description "2 input 2 output flyback potential transformer")
      (libsource (lib "") (part "PT_FLYBACK_2IN-2OUT_1"))
    )
    (comp (ref "TP1") (value "GRID_L") (footprint "TP90-50") (libsource (lib "") (part "TP_1")))
    (comp (ref "TP2") (value "GRID_N") (footprint "TP90-50") (libsource (lib "") (part "TP_1")))
    (comp (ref "TP3") (value "PV+") (footprint "TP90-50") (libsource (lib "") (part "TP_1")))
    (comp (ref "TP4") (value "PV-") (footprint "TP90-50") (libsource (lib "") (part "TP_1")))
    (comp (ref "TP5") (value "OUT_U") (footprint "TP90-50") (libsource (lib "MeoLib_v2") (part "TP")))
    (comp (ref "TP6") (value "OUT_V") (footprint "TP90-50") (libsource (lib "MeoLib_v2") (part "TP")))
    (comp (ref "TP7") (value "OUT_W") (footprint "TP90-50") (libsource (lib "MeoLib_v2") (part "TP")))
    (comp (ref "XT1") (value "XTAL") (footprint "XTAL-49S-SMD") (libsource (lib "MeoLib_v2") (part "XTAL")))
    (comp (ref "XT2") (value "XTAL") (footprint "XTAL-49S-SMD") (libsource (lib "") (part "XTAL_1")))
  )
  (nets
    (net (code "1") (name "+5") (class "Default")
      (node (ref "C102") (pin "1") (pinfunction "1_1") (pintype "passive"))
      (node (ref "C112") (pin "1") (pinfunction "1_1") (pintype "passive"))
      (node (ref "C116") (pin "1") (pinfunction "1_1") (pintype "passive"))
      (node (ref "C119") (pin "1") (pinfunction "1_1") (pintype "passive"))
      (node (ref "C120") (pin "1") (pinfunction "1_1") (pintype "passive"))
      (node (ref "C128") (pin "1") (pinfunction "1_1") (pintype "passive"))
      (node (ref "C141") (pin "1") (pinfunction "1_1") (pintype "passive"))
      (node (ref "C149") (pin "1") (pinfunction "1_1") (pintype "passive"))
      (node (ref "C18") (pin "1") (pinfunction "1_1") (pintype "passive"))
      (node (ref "C39") (pin "1") (pinfunction "1_1") (pintype "passive"))
      (node (ref "C52") (pin "1") (pinfunction "1_1") (pintype "passive"))
      (node (ref "C72") (pin "1") (pinfunction "1_1") (pintype "passive"))
      (node (ref "C86") (pin "1") (pinfunction "1_1") (pintype "passive"))
      (node (ref "C9") (pin "1") (pinfunction "1_1") (pintype "passive"))
      (node (ref "IC1") (pin "4") (pinfunction "VDD_4") (pintype "power_in"))
      (node (ref "IC10") (pin "8") (pinfunction "VCC_8") (pintype "passive"))
      (node (ref "IC13") (pin "8") (pinfunction "VCC_8") (pintype "passive"))
      (node (ref "IC15") (pin "8") (pinfunction "VCC_8") (pintype "passive"))
      (node (ref "IC16") (pin "4") (pinfunction "VDD_4") (pintype "power_in"))
      (node (ref "IC17") (pin "4") (pinfunction "VDD_4") (pintype "power_in"))
      (node (ref "IC7") (pin "4") (pinfunction "VDD_4") (pintype "power_in"))
      (node (ref "R106") (pin "2") (pinfunction "2_2") (pintype "passive"))
      (node (ref "R116") (pin "2") (pinfunction "2_2") (pintype "passive"))
      (node (ref "R129") (pin "2") (pinfunction "2_2") (pintype "passive"))
      (node (ref "R141") (pin "2") (pinfunction "2_2") (pintype "passive"))
    )
    (net (code "2") (name "+15") (class "Default")
      (node (ref "C1") (pin "1") (pinfunction "1_1") (pintype "passive"))
      (node (ref "D16") (pin "1") (pinfunction "A_1") (pintype "passive"))
      (node (ref "D27") (pin "1") (pinfunction "A_1") (pintype "passive"))
      (node (ref "J1") (pin "1") (pinfunction "1_1") (pintype "passive"))
      (node (ref "J3") (pin "1") (pinfunction "1_1") (pintype "passive"))
      (node (ref "J4") (pin "10") (pinfunction "10_10") (pintype "passive"))
      (node (ref "J5") (pin "2") (pinfunction "2_2") (pintype "passive"))
      (node (ref "L11") (pin "2") (pinfunction "2_2") (pintype "passive"))
      (node (ref "L8") (pin "2") (pinfunction "2_2") (pintype "passive"))
      (node (ref "L9") (pin "2") (pinfunction "2_2") (pintype "passive"))
      (node (ref "R20") (pin "1") (pinfunction "1_1") (pintype "passive"))
      (node (ref "R57") (pin "1") (pinfunction "1_1") (pintype "passive"))
    )
    (net (code "3") (name "/ADC") (class "Default")
      (node (ref "IC19") (pin "10") (pinfunction "PC2_10") (pintype "bidirectional"))
      (node (ref "IC19") (pin "11") (pinfunction "PC3_11") (pintype "bidirectional"))
      (node (ref "IC19") (pin "15") (pinfunction "PA1_15") (pintype "bidirectional"))
      (node (ref "IC19") (pin "16") (pinfunction "PA2_16") (pintype "bidirectional"))
      (node (ref "IC19") (pin "17") (pinfunction "PA3_17") (pintype "bidirectional"))
      (node (ref "IC19") (pin "20") (pinfunction "PA4_20") (pintype "bidirectional"))
      (node (ref "IC19") (pin "21") (pinfunction "PA5_21") (pintype "bidirectional"))
      (node (ref "IC19") (pin "22") (pinfunction "PA6_22") (pintype "bidirectional"))
      (node (ref "IC19") (pin "23") (pinfunction "PA7_23") (pintype "bidirectional"))
      (node (ref "IC19") (pin "24") (pinfunction "PC4_24") (pintype "bidirectional"))
      (node (ref "IC19") (pin "25") (pinfunction "PC5_25") (pintype "bidirectional"))
      (node (ref "IC19") (pin "26") (pinfunction "PB0_26") (pintype "bidirectional"))
      (node (ref "IC19") (pin "27") (pinfunction "PB1_27") (pintype "bidirectional"))
      (node (ref "IC19") (pin "8") (pinfunction "PC0_8") (pintype "bidirectional"))
      (node (ref "IC19") (pin "9") (pinfunction "PC1_9") (pintype "bidirectional"))
    )
    (net (code "4") (name "/TIM1_BRK") (class "Default")
      (node (ref "IC19") (pin "33") (pinfunction "PB12_33") (pintype "bidirectional"))
    )
    (net (code "5") (name "/TIM1_CH") (class "Default")
      (node (ref "IC19") (pin "34") (pinfunction "PB13_34") (pintype "bidirectional"))
      (node (ref "IC19") (pin "35") (pinfunction "PB14_35") (pintype "bidirectional"))
      (node (ref "IC19") (pin "36") (pinfunction "PB15_36") (pintype "bidirectional"))
      (node (ref "IC19") (pin "41") (pinfunction "PA8_41") (pintype "bidirectional"))
      (node (ref "IC19") (pin "42") (pinfunction "PA9_42") (pintype "bidirectional"))
      (node (ref "IC19") (pin "43") (pinfunction "PA10_43") (pintype "bidirectional"))
    )
    (net (code "6") (name "/TIM1_ETR") (class "Default")
      (node (ref "IC19") (pin "45") (pinfunction "PA12_45") (pintype "bidirectional"))
    )
    (net (code "7") (name "/TIM2_CH") (class "Default")
      (node (ref "IC19") (pin "29") (pinfunction "PB10_29") (pintype "bidirectional"))
      (node (ref "IC19") (pin "30") (pinfunction "PB11_30") (pintype "bidirectional"))
    )
    (net (code "8") (name "/TIM2_ETR") (class "Default")
      (node (ref "IC19") (pin "14") (pinfunction "PA0-WKUP_14") (pintype "bidirectional"))
    )
    (net (code "9") (name "BOOT") (class "Default")
      (node (ref "IC19") (pin "60") (pinfunction "BOOT0_60") (pintype "input"))
      (node (ref "J5") (pin "8") (pinfunction "8_8") (pintype "passive"))
      (node (ref "R122") (pin "1") (pinfunction "1_1") (pintype "passive"))
    )
    (net (code "10") (name "BULK+") (class "Default")
      (node (ref "C122") (pin "1") (pinfunction "1_1") (pintype "passive"))
      (node (ref "C129") (pin "1") (pinfunction "1_1") (pintype "passive"))
      (node (ref "C143") (pin "1") (pinfunction "1_1") (pintype "passive"))
    )
    (net (code "11") (name "DRV_A") (class "Default")
      (node (ref "IC6") (pin "7") (pinfunction "OUTA_7") (pintype "output"))
      (node (ref "R53") (pin "2") (pinfunction "2_2") (pintype "passive"))
    )
    (net (code "12") (name "DRV_B") (class "Default")
      (node (ref "IC6") (pin "5") (pinfunction "OUTB_5") (pintype "output"))
      (node (ref "R45") (pin "2") (pinfunction "2_2") (pintype "passive"))
    )
    (net (code "13") (name "EXT_IO1") (class "Default")
      (node (ref "J4") (pin "7") (pinfunction "7_7") (pintype "passive"))
      (node (ref "J5") (pin "7") (pinfunction "7_7") (pintype "passive"))
    )
    (net (code "14") (name "EXT_IO2") (class "Default")
      (node (ref "J4") (pin "9") (pinfunction "9_9") (pintype "passive"))
      (node (ref "J5") (pin "9") (pinfunction "9_9") (pintype "passive"))
    )
    (net (code "15") (name "EXT_IO3") (class "Default")
      (node (ref "J4") (pin "8") (pinfunction "8_8") (pintype "passive"))
      (node (ref "J5") (pin "10") (pinfunction "10_10") (pintype "passive"))
    )
    (net (code "16") (name "GD_L_FTLD") (class "Default")
      (node (ref "C14") (pin "2") (pinfunction "2_2") (pintype "passive"))
      (node (ref "C8") (pin "2") (pinfunction "2_2") (pintype "passive"))
      (node (ref "D4") (pin "2") (pinfunction "2_2") (pintype "passive"))
      (node (ref "L3") (pin "3") (pinfunction "3_3") (pintype "passive"))
      (node (ref "R13") (pin "1") (pinfunction "1_1") (pintype "passive"))
      (node (ref "R9") (pin "2") (pinfunction "2_2") (pintype "passive"))
      (node (ref "RL1") (pin "3") (pinfunction "NO_3") (pintype "passive"))
    )
    (net (code "17") (name "GD_N_FTLD") (class "Default")
      (node (ref "C14") (pin "1") (pinfunction "1_1") (pintype "passive"))
      (node (ref "C23") (pin "1") (pinfunction "1_1") (pintype "passive"))
      (node (ref "D14") (pin "1") (pinfunction "1_1") (pintype "passive"))
      (node (ref "DB2") (pin "2") (pinfunction "AC1_2") (pintype "passive"))
      (node (ref "L3") (pin "2") (pinfunction "2_2") (pintype "passive"))
      (node (ref "R1") (pin "1") (pinfunction "1_1") (pintype "passive"))
      (node (ref "RL2") (pin "3") (pinfunction "NO_3") (pintype "passive"))
    )
    (net (code "18") (name "GND") (class "Default")
      (node (ref "B1") (pin "2") (pintype "passive"))
      (node (ref "C1") (pin "2") (pinfunction "2_2") (pintype "passive"))
      (node (ref "C100") (pin "1") (pinfunction "1_1") (pintype "passive"))
      (node (ref "C101") (pin "2") (pinfunction "2_2") (pintype "passive"))
      (node (ref "C102") (pin "2") (pinfunction "2_2") (pintype "passive"))
      (node (ref "C103") (pin "1") (pinfunction "1_1") (pintype "passive"))
      (node (ref "C104") (pin "2") (pinfunction "2_2") (pintype "passive"))
      (node (ref "C105") (pin "2") (pinfunction "2_2") (pintype "passive"))
      (node (ref "C106") (pin "2") (pinfunction "2_2") (pintype "passive"))
      (node (ref "C107") (pin "1") (pinfunction "1_1") (pintype "passive"))
      (node (ref "C108") (pin "1") (pinfunction "1_1") (pintype "passive"))
      (node (ref "C109") (pin "1") (pinfunction "1_1") (pintype "passive"))
      (node (ref "C110") (pin "2") (pinfunction "2_2") (pintype "passive"))
      (node (ref "C111") (pin "1") (pinfunction "1_1") (pintype "passive"))
      (node (ref "C112") (pin "2") (pinfunction "2_2") (pintype "passive"))
      (node (ref "C113") (pin "2") (pinfunction "2_2") (pintype "passive"))
      (node (ref "C114") (pin "2") (pinfunction "2_2") (pintype "passive"))
      (node (ref "C115") (pin "2") (pinfunction "2_2") (pintype "passive"))
      (node (ref "C116") (pin "2") (pinfunction "2_2") (pintype "passive"))
      (node (ref "C117") (pin "1") (pinfunction "1_1") (pintype "passive"))
      (node (ref "C118") (pin "2") (pinfunction "2_2") (pintype "passive"))
      (node (ref "C119") (pin "2") (pinfunction "2_2") (pintype "passive"))
      (node (ref "C120") (pin "2") (pinfunction "2_2") (pintype "passive"))
      (node (ref "C121") (pin "1") (pinfunction "1_1") (pintype "passive"))
      (node (ref "C123") (pin "2") (pinfunction "2_2") (pintype "passive"))
      (node (ref "C125") (pin "1") (pinfunction "1_1") (pintype "passive"))
      (node (ref "C126") (pin "1") (pinfunction "1_1") (pintype "passive"))
      (node (ref "C127") (pin "2") (pinfunction "2_2") (pintype "passive"))
      (node (ref "C128") (pin "2") (pinfunction "2_2") (pintype "passive"))
      (node (ref "C130") (pin "2") (pinfunction "2_2") (pintype "passive"))
      (node (ref "C131") (pin "2") (pinfunction "2_2") (pintype "passive"))
      (node (ref "C132") (pin "2") (pinfunction "2_2") (pintype "passive"))
      (node (ref "C133") (pin "2") (pinfunction "2_2") (pintype "passive"))
      (node (ref "C134") (pin "2") (pinfunction "2_2") (pintype "passive"))
      (node (ref "C136") (pin "2") (pinfunction "2_2") (pintype "passive"))
      (node (ref "C137") (pin "1") (pinfunction "1_1") (pintype "passive"))
      (node (ref "C138") (pin "1") (pinfunction "1_1") (pintype "passive"))
      (node (ref "C141") (pin "2") (pinfunction "2_2") (pintype "passive"))
      (node (ref "C142") (pin "2") (pinfunction "2_2") (pintype "passive"))
      (node (ref "C144") (pin "2") (pinfunction "2_2") (pintype "passive"))
      (node (ref "C145") (pin "1") (pinfunction "1_1") (pintype "passive"))
      (node (ref "C146") (pin "2") (pinfunction "2_2") (pintype "passive"))
      (node (ref "C147") (pin "1") (pinfunction "1_1") (pintype "passive"))
      (node (ref "C148") (pin "2") (pinfunction "2_2") (pintype "passive"))
      (node (ref "C149") (pin "2") (pinfunction "2_2") (pintype "passive"))
      (node (ref "C15") (pin "2") (pinfunction "2_2") (pintype "passive"))
      (node (ref "C150") (pin "1") (pinfunction "1_1") (pintype "passive"))
      (node (ref "C151") (pin "2") (pinfunction "2_2") (pintype "passive"))
      (node (ref "C17") (pin "1") (pinfunction "1_1") (pintype "passive"))
      (node (ref "C18") (pin "2") (pinfunction "2_2") (pintype "passive"))
      (node (ref "C2") (pin "2") (pinfunction "2_2") (pintype "passive"))
      (node (ref "C27") (pin "2") (pinfunction "2_2") (pintype "passive"))
      (node (ref "C28") (pin "1") (pinfunction "1_1") (pintype "passive"))
      (node (ref "C3") (pin "2") (pinfunction "2_2") (pintype "passive"))
      (node (ref "C30") (pin "1") (pinfunction "1_1") (pintype "passive"))
      (node (ref "C31") (pin "2") (pinfunction "2_2") (pintype "passive"))
      (node (ref "C32") (pin "2") (pinfunction "2_2") (pintype "passive"))
      (node (ref "C33") (pin "1") (pinfunction "1_1") (pintype "passive"))
      (node (ref "C34") (pin "2") (pinfunction "2_2") (pintype "passive"))
      (node (ref "C37") (pin "2") (pinfunction "2_2") (pintype "passive"))
      (node (ref "C39") (pin "2") (pinfunction "2_2") (pintype "passive"))
      (node (ref "C4") (pin "2") (pinfunction "2_2") (pintype "passive"))
      (node (ref "C40") (pin "1") (pinfunction "1_1") (pintype "passive"))
      (node (ref "C41") (pin "1") (pinfunction "1_1") (pintype "passive"))
      (node (ref "C42") (pin "2") (pinfunction "2_2") (pintype "passive"))
      (node (ref "C43") (pin "2") (pinfunction "2_2") (pintype "passive"))
      (node (ref "C44") (pin "1") (pinfunction "1_1") (pintype "passive"))
      (node (ref "C46") (pin "2") (pinfunction "2_2") (pintype "passive"))
      (node (ref "C47") (pin "2") (pinfunction "2_2") (pintype "passive"))
      (node (ref "C48") (pin "2") (pinfunction "2_2") (pintype "passive"))
      (node (ref "C49") (pin "2") (pinfunction "2_2") (pintype "passive"))
      (node (ref "C50") (pin "2") (pinfunction "2_2") (pintype "passive"))
      (node (ref "C52") (pin "2") (pinfunction "2_2") (pintype "passive"))
      (node (ref "C53") (pin "1") (pinfunction "1_1") (pintype "passive"))
      (node (ref "C54") (pin "1") (pinfunction "1_1") (pintype "passive"))
      (node (ref "C56") (pin "1") (pinfunction "1_1") (pintype "passive"))
      (node (ref "C57") (pin "2") (pinfunction "2_2") (pintype "passive"))
      (node (ref "C6") (pin "2") (pinfunction "2_2") (pintype "passive"))
      (node (ref "C60") (pin "2") (pinfunction "2_2") (pintype "passive"))
      (node (ref "C63") (pin "2") (pinfunction "2_2") (pintype "passive"))
      (node (ref "C64") (pin "2") (pinfunction "2_2") (pintype "passive"))
      (node (ref "C65") (pin "2") (pinfunction "2_2") (pintype "passive"))
      (node (ref "C66") (pin "1") (pinfunction "1_1") (pintype "passive"))
      (node (ref "C67") (pin "1") (pinfunction "1_1") (pintype "passive"))
      (node (ref "C68") (pin "2") (pinfunction "2_2") (pintype "passive"))
      (node (ref "C7") (pin "2") (pinfunction "2_2") (pintype "passive"))
      (node (ref "C70") (pin "2") (pinfunction "2_2") (pintype "passive"))
      (node (ref "C71") (pin "2") (pinfunction "2_2") (pintype "passive"))
      (node (ref "C72") (pin "2") (pinfunction "2_2") (pintype "passive"))
      (node (ref "C73") (pin "2") (pinfunction "2_2") (pintype "passive"))
      (node (ref "C74") (pin "1") (pinfunction "1_1") (pintype "passive"))
      (node (ref "C75") (pin "2") (pinfunction "2_2") (pintype "passive"))
      (node (ref "C76") (pin "2") (pinfunction "2_2") (pintype "passive"))
      (node (ref "C77") (pin "1") (pinfunction "1_1") (pintype "passive"))
      (node (ref "C78") (pin "1") (pinfunction "1_1") (pintype "passive"))
      (node (ref "C79") (pin "2") (pinfunction "2_2") (pintype "passive"))
      (node (ref "C82") (pin "2") (pinfunction "2_2") (pintype "passive"))
      (node (ref "C86") (pin "2") (pinfunction "2_2") (pintype "passive"))
      (node (ref "C87") (pin "1") (pinfunction "1_1") (pintype "passive"))
      (node (ref "C89") (pin "2") (pinfunction "2_2") (pintype "passive"))
      (node (ref "C9") (pin "2") (pinfunction "2_2") (pintype "passive"))
      (node (ref "C90") (pin "2") (pinfunction "2_2") (pintype "passive"))
      (node (ref "C91") (pin "1") (pinfunction "1_1") (pintype "passive"))
      (node (ref "C92") (pin "1") (pinfunction "1_1") (pintype "passive"))
      (node (ref "C93") (pin "2") (pinfunction "2_2") (pintype "passive"))
      (node (ref "C95") (pin "2") (pinfunction "2_2") (pintype "passive"))
      (node (ref "C96") (pin "1") (pinfunction "1_1") (pintype "passive"))
      (node (ref "C97") (pin "2") (pinfunction "2_2") (pintype "passive"))
      (node (ref "C99") (pin "1") (pinfunction "1_1") (pintype "passive"))
      (node (ref "DZ3") (pin "1") (pinfunction "A_1") (pintype "passive"))
      (node (ref "DZ5") (pin "1") (pinfunction "A_1") (pintype "passive"))
      (node (ref "IC1") (pin "11") (pinfunction "VSS_11") (pintype "power_in"))
      (node (ref "IC10") (pin "5") (pinfunction "GND_5") (pintype "passive"))
      (node (ref "IC11") (pin "15") (pinfunction "COM_15") (pintype "power_in"))
      (node (ref "IC12") (pin "2") (pinfunction "Ground_2") (pintype "power_in"))
      (node (ref "IC13") (pin "5") (pinfunction "GND_5") (pintype "passive"))
      (node (ref "IC14") (pin "2") (pinfunction "Ground_2") (pintype "power_in"))
      (node (ref "IC15") (pin "5") (pinfunction "GND_5") (pintype "passive"))
      (node (ref "IC16") (pin "11") (pinfunction "VSS_11") (pintype "power_in"))
      (node (ref "IC17") (pin "11") (pinfunction "VSS_11") (pintype "power_in"))
      (node (ref "IC18") (pin "15") (pinfunction "GND_15") (pintype "power_in"))
      (node (ref "IC19") (pin "12") (pinfunction "VSSA_12") (pintype "power_in"))
      (node (ref "IC19") (pin "18") (pinfunction "VSS_4_18") (pintype "power_in"))
      (node (ref "IC19") (pin "31") (pinfunction "VSS_1_31") (pintype "power_in"))
      (node (ref "IC19") (pin "47") (pinfunction "VSS_2_47") (pintype "power_in"))
      (node (ref "IC19") (pin "63") (pinfunction "VSS_3_63") (pintype "power_in"))
      (node (ref "IC2") (pin "2") (pinfunction "K_2") (pintype "passive"))
      (node (ref "IC3") (pin "2") (pinfunction "K_2") (pintype "passive"))
      (node (ref "IC6") (pin "3") (pinfunction "GND_3") (pintype "power_in"))
      (node (ref "IC7") (pin "11") (pinfunction "VSS_11") (pintype "power_in"))
      (node (ref "IC9") (pin "2") (pinfunction "Ground_2") (pintype "power_in"))
      (node (ref "J3") (pin "2") (pinfunction "2_2") (pintype "passive"))
      (node (ref "J3") (pin "5") (pinfunction "5_5") (pintype "passive"))
      (node (ref "J4") (pin "5") (pinfunction "5_5") (pintype "passive"))
      (node (ref "J4") (pin "6") (pinfunction "6_6") (pintype "passive"))
      (node (ref "J5") (pin "4") (pinfunction "4_4") (pintype "passive"))
      (node (ref "J5") (pin "5") (pinfunction "5_5") (pintype "passive"))
      (node (ref "Q1") (pin "3") (pinfunction "S_3") (pintype "passive"))
      (node (ref "Q2") (pin "3") (pinfunction "S_3") (pintype "passive"))
      (node (ref "Q3") (pin "3") (pinfunction "S_3") (pintype "passive"))
      (node (ref "Q5") (pin "3") (pinfunction "S_3") (pintype "passive"))
      (node (ref "Q6") (pin "2") (pinfunction "C_2") (pintype "passive"))
      (node (ref "Q7") (pin "2") (pinfunction "C_2") (pintype "passive"))
      (node (ref "R102") (pin "1") (pinfunction "1_1") (pintype "passive"))
      (node (ref "R104") (pin "1") (pinfunction "1_1") (pintype "passive"))
      (node (ref "R113") (pin "1") (pinfunction "1_1") (pintype "passive"))
      (node (ref "R115") (pin "1") (pinfunction "1_1") (pintype "passive"))
      (node (ref "R122") (pin "2") (pinfunction "2_2") (pintype "passive"))
      (node (ref "R124") (pin "1") (pinfunction "1_1") (pintype "passive"))
      (node (ref "R130") (pin "1") (pinfunction "1_1") (pintype "passive"))
      (node (ref "R132") (pin "1") (pinfunction "1_1") (pintype "passive"))
      (node (ref "R138") (pin "2") (pinfunction "2_2") (pintype "passive"))
      (node (ref "R140") (pin "1") (pinfunction "1_1") (pintype "passive"))
      (node (ref "R142") (pin "1") (pinfunction "1_1") (pintype "passive"))
      (node (ref "R146") (pin "1") (pinfunction "1_1") (pintype "passive"))
      (node (ref "R147") (pin "1") (pinfunction "1_1") (pintype "passive"))
      (node (ref "R153") (pin "1") (pinfunction "1_1") (pintype "passive"))
      (node (ref "R17") (pin "1") (pinfunction "1_1") (pintype "passive"))
      (node (ref "R18") (pin "1") (pinfunction "1_1") (pintype "passive"))
      (node (ref "R24") (pin "1") (pinfunction "1_1") (pintype "passive"))
      (node (ref "R29") (pin "2") (pinfunction "2_2") (pintype "passive"))
      (node (ref "R31") (pin "1") (pinfunction "1_1") (pintype "passive"))
      (node (ref "R43") (pin "1") (pinfunction "1_1") (pintype "passive"))
      (node (ref "R64") (pin "1") (pinfunction "1_1") (pintype "passive"))
      (node (ref "R67") (pin "2") (pinfunction "2_2") (pintype "passive"))
      (node (ref "R69") (pin "2") (pinfunction "2_2") (pintype "passive"))
      (node (ref "R7") (pin "1") (pinfunction "1_1") (pintype "passive"))
      (node (ref "R75") (pin "1") (pinfunction "1_1") (pintype "passive"))
      (node (ref "R76") (pin "1") (pinfunction "1_1") (pintype "passive"))
      (node (ref "R77") (pin "2") (pinfunction "2_2") (pintype "passive"))
      (node (ref "R8") (pin "1") (pinfunction "1_1") (pintype "passive"))
      (node (ref "R81") (pin "2") (pinfunction "2_2") (pintype "passive"))
      (node (ref "R84") (pin "1") (pinfunction "1_1") (pintype "passive"))
      (node (ref "R85") (pin "1") (pinfunction "1_1") (pintype "passive"))
      (node (ref "R90") (pin "2") (pinfunction "2_2") (pintype "passive"))
      (node (ref "R92") (pin "1") (pinfunction "1_1") (pintype "passive"))
      (node (ref "R96") (pin "1") (pinfunction "1_1") (pintype "passive"))
      (node (ref "T1") (pin "4") (pinfunction "4_4") (pintype "passive"))
      (node (ref "T2") (pin "4") (pinfunction "4_4") (pintype "passive"))
    )
    (net (code "19") (name "G_PSGD") (class "Default")
      (node (ref "C10") (pin "2") (pinfunction "2_2") (pintype "passive"))
      (node (ref "C11") (pin "2") (pinfunction "2_2") (pintype "passive"))
      (node (ref "C24") (pin "1") (pinfunction "1_1") (pintype "passive"))
      (node (ref "IC2") (pin "3") (pinfunction "E_3") (pintype "passive"))
      (node (ref "IC4") (pin "5") (pinfunction "Source_5") (pintype "passive"))
      (node (ref "IC4") (pin "6") (pinfunction "Source_6") (pintype "passive"))
      (node (ref "IC4") (pin "7") (pinfunction "Source_7") (pintype "passive"))
      (node (ref "IC4") (pin "8") (pinfunction "Source_8") (pintype "passive"))
      (node (ref "R27") (pin "1") (pinfunction "1_1") (pintype "passive"))
    )
    (net (code "20") (name "G_PSPV") (class "Default")
      (node (ref "C12") (pin "2") (pinfunction "2_2") (pintype "passive"))
      (node (ref "C20") (pin "2") (pinfunction "2_2") (pintype "passive"))
      (node (ref "C25") (pin "1") (pinfunction "1_1") (pintype "passive"))
      (node (ref "IC3") (pin "3") (pinfunction "E_3") (pintype "passive"))
      (node (ref "IC5") (pin "5") (pinfunction "Source_5") (pintype "passive"))
      (node (ref "IC5") (pin "6") (pinfunction "Source_6") (pintype "passive"))
      (node (ref "IC5") (pin "7") (pinfunction "Source_7") (pintype "passive"))
      (node (ref "IC5") (pin "8") (pinfunction "Source_8") (pintype "passive"))
      (node (ref "R28") (pin "2") (pinfunction "2_2") (pintype "passive"))
    )
    (net (code "21") (name "HV_SUPP+") (class "Default")
      (node (ref "C35") (pin "2") (pinfunction "2_2") (pintype "passive"))
      (node (ref "C37") (pin "1") (pinfunction "1_1") (pintype "passive"))
      (node (ref "C42") (pin "1") (pinfunction "1_1") (pintype "passive"))
      (node (ref "C43") (pin "1") (pinfunction "1_1") (pintype "passive"))
      (node (ref "C87") (pin "2") (pinfunction "2_2") (pintype "passive"))
      (node (ref "C96") (pin "2") (pinfunction "2_2") (pintype "passive"))
      (node (ref "D17") (pin "2") (pinfunction "K_2") (pintype "passive"))
      (node (ref "IC11") (pin "3") (pinfunction "P_3") (pintype "input"))
      (node (ref "L2") (pin "2") (pinfunction "2_2") (pintype "passive"))
      (node (ref "R44") (pin "1") (pinfunction "1_1") (pintype "passive"))
      (node (ref "R70") (pin "2") (pinfunction "2_2") (pintype "passive"))
    )
    (net (code "22") (name "IBC_TMP") (class "Default")
      (node (ref "C64") (pin "1") (pinfunction "1_1") (pintype "passive"))
      (node (ref "J2") (pin "2") (pinfunction "2_2") (pintype "passive"))
      (node (ref "R96") (pin "2") (pinfunction "2_2") (pintype "passive"))
    )
    (net (code "23") (name "IBUS_S") (class "Default")
      (node (ref "C142") (pin "1") (pinfunction "1_1") (pintype "passive"))
      (node (ref "R144") (pin "1") (pinfunction "1_1") (pintype "passive"))
      (node (ref "R146") (pin "2") (pinfunction "2_2") (pintype "passive"))
    )
    (net (code "24") (name "IGD_S") (class "Default")
      (node (ref "C27") (pin "1") (pinfunction "1_1") (pintype "passive"))
      (node (ref "R30") (pin "1") (pinfunction "1_1") (pintype "passive"))
      (node (ref "R31") (pin "2") (pinfunction "2_2") (pintype "passive"))
    )
    (net (code "25") (name "IPM_TMP") (class "Default")
      (node (ref "C70") (pin "1") (pinfunction "1_1") (pintype "passive"))
      (node (ref "IC11") (pin "2") (pinfunction "RTH_2") (pintype "passive"))
      (node (ref "R102") (pin "2") (pinfunction "2_2") (pintype "passive"))
    )
    (net (code "26") (name "IPV_S") (class "Default")
      (node (ref "C63") (pin "1") (pinfunction "1_1") (pintype "passive"))
      (node (ref "R91") (pin "1") (pinfunction "1_1") (pintype "passive"))
      (node (ref "R92") (pin "2") (pinfunction "2_2") (pintype "passive"))
    )
    (net (code "27") (name "IU_S") (class "Default")
      (node (ref "C82") (pin "1") (pinfunction "1_1") (pintype "passive"))
      (node (ref "R103") (pin "1") (pinfunction "1_1") (pintype "passive"))
      (node (ref "R104") (pin "2") (pinfunction "2_2") (pintype "passive"))
    )
    (net (code "28") (name "IV_S") (class "Default")
      (node (ref "C97") (pin "1") (pinfunction "1_1") (pintype "passive"))
      (node (ref "R111") (pin "1") (pinfunction "1_1") (pintype "passive"))
      (node (ref "R113") (pin "2") (pinfunction "2_2") (pintype "passive"))
    )
    (net (code "29") (name "IW_S") (class "Default")
      (node (ref "C110") (pin "1") (pinfunction "1_1") (pintype "passive"))
      (node (ref "R121") (pin "1") (pinfunction "1_1") (pintype "passive"))
      (node (ref "R124") (pin "2") (pinfunction "2_2") (pintype "passive"))
    )
    (net (code "30") (name "NRST") (class "Default")
      (node (ref "C121") (pin "2") (pinfunction "2_2") (pintype "passive"))
      (node (ref "IC19") (pin "7") (pinfunction "NRST_7") (pintype "bidirectional"))
      (node (ref "J5") (pin "6") (pinfunction "6_6") (pintype "passive"))
      (node (ref "R125") (pin "1") (pinfunction "1_1") (pintype "passive"))
      (node (ref "R138") (pin "1") (pinfunction "1_1") (pintype "passive"))
    )
    (net (code "31") (name "Net-(C13-Pad1)") (class "Default")
      (node (ref "C13") (pin "1") (pinfunction "1_1") (pintype "passive"))
      (node (ref "C22") (pin "1") (pinfunction "1_1") (pintype "passive"))
      (node (ref "D13") (pin "1") (pinfunction "1_1") (pintype "passive"))
      (node (ref "D9") (pin "1") (pinfunction "1_1") (pintype "passive"))
      (node (ref "L3") (pin "1") (pinfunction "1_1") (pintype "passive"))
      (node (ref "R22") (pin "2") (pinfunction "2_2") (pintype "passive"))
      (node (ref "TP2") (pin "0") (pinfunction "0_0") (pintype "passive"))
    )
    (net (code "32") (name "Net-(C13-Pad2)") (class "Default")
      (node (ref "C13") (pin "2") (pinfunction "2_2") (pintype "passive"))
      (node (ref "C5") (pin "2") (pinfunction "2_2") (pintype "passive"))
      (node (ref "D1") (pin "2") (pinfunction "2_2") (pintype "passive"))
      (node (ref "D9") (pin "2") (pinfunction "2_2") (pintype "passive"))
      (node (ref "L3") (pin "4") (pinfunction "4_4") (pintype "passive"))
      (node (ref "R12") (pin "1") (pinfunction "1_1") (pintype "passive"))
      (node (ref "TP1") (pin "0") (pinfunction "0_0") (pintype "passive"))
    )
    (net (code "33") (name "Net-(C21-Pad1)") (class "Default")
      (node (ref "C21") (pin "1") (pinfunction "1_1") (pintype "passive"))
      (node (ref "F1") (pin "1") (pinfunction "1_1") (pintype "passive"))
      (node (ref "L1") (pin "1") (pinfunction "1_1") (pintype "passive"))
    )
    (net (code "34") (name "Net-(C22-Pad2)") (class "Default")
      (node (ref "C22") (pin "2") (pinfunction "2_2") (pintype "passive"))
      (node (ref "C5") (pin "1") (pinfunction "1_1") (pintype "passive"))
      (node (ref "D1") (pin "1") (pinfunction "1_1") (pintype "passive"))
      (node (ref "D13") (pin "2") (pinfunction "2_2") (pintype "passive"))
      (node (ref "H1") (pin "0") (pinfunction "0_0") (pintype "passive"))
    )
    (net (code "35") (name "Net-(C23-Pad2)") (class "Default")
      (node (ref "C23") (pin "2") (pinfunction "2_2") (pintype "passive"))
      (node (ref "C8") (pin "1") (pinfunction "1_1") (pintype "passive"))
      (node (ref "D14") (pin "2") (pinfunction "2_2") (pintype "passive"))
      (node (ref "D4") (pin "1") (pinfunction "1_1") (pintype "passive"))
      (node (ref "H2") (pin "0") (pinfunction "0_0") (pintype "passive"))
    )
    (net (code "36") (name "Net-(C26-Pad1)") (class "Default")
      (node (ref "C26") (pin "1") (pinfunction "1_1") (pintype "passive"))
      (node (ref "R24") (pin "2") (pinfunction "2_2") (pintype "passive"))
      (node (ref "R25") (pin "1") (pinfunction "1_1") (pintype "passive"))
    )
    (net (code "37") (name "Net-(C26-Pad2)") (class "Default")
      (node (ref "C26") (pin "2") (pinfunction "2_2") (pintype "passive"))
      (node (ref "R32") (pin "1") (pinfunction "1_1") (pintype "passive"))
      (node (ref "R33") (pin "1") (pinfunction "1_1") (pintype "passive"))
    )
    (net (code "38") (name "Net-(C35-Pad1)") (class "Default")
      (node (ref "C35") (pin "1") (pinfunction "1_1") (pintype "passive"))
      (node (ref "C54") (pin "2") (pinfunction "2_2") (pintype "passive"))
      (node (ref "H3") (pin "0") (pinfunction "0_0") (pintype "passive"))
    )
    (net (code "39") (name "Net-(C36-Pad1)") (class "Default")
      (node (ref "C36") (pin "1") (pinfunction "1_1") (pintype "passive"))
      (node (ref "C58") (pin "2") (pinfunction "2_2") (pintype "passive"))
      (node (ref "D18") (pin "1") (pinfunction "1_1") (pintype "passive"))
      (node (ref "D25") (pin "2") (pinfunction "2_2") (pintype "passive"))
      (node (ref "H4") (pin "0") (pinfunction "0_0") (pintype "passive"))
    )
    (net (code "40") (name "Net-(C38-Pad1)") (class "Default")
      (node (ref "C38") (pin "1") (pinfunction "1_1") (pintype "passive"))
      (node (ref "C59") (pin "2") (pinfunction "2_2") (pintype "passive"))
      (node (ref "D19") (pin "1") (pinfunction "1_1") (pintype "passive"))
      (node (ref "D26") (pin "2") (pinfunction "2_2") (pintype "passive"))
      (node (ref "H5") (pin "0") (pinfunction "0_0") (pintype "passive"))
    )
    (net (code "41") (name "Net-(C44-Pad2)") (class "Default")
      (node (ref "C44") (pin "2") (pinfunction "2_2") (pintype "passive"))
      (node (ref "R58") (pin "1") (pinfunction "1_1") (pintype "passive"))
    )
    (net (code "42") (name "Net-(C53-Pad2)") (class "Default")
      (node (ref "C53") (pin "2") (pinfunction "2_2") (pintype "passive"))
      (node (ref "R54") (pin "1") (pinfunction "1_1") (pintype "passive"))
    )
    (net (code "43") (name "Net-(C62-Pad1)") (class "Default")
      (node (ref "C62") (pin "1") (pinfunction "1_1") (pintype "passive"))
      (node (ref "R85") (pin "2") (pinfunction "2_2") (pintype "passive"))
      (node (ref "R86") (pin "1") (pinfunction "1_1") (pintype "passive"))
    )
    (net (code "44") (name "Net-(C62-Pad2)") (class "Default")
      (node (ref "C62") (pin "2") (pinfunction "2_2") (pintype "passive"))
      (node (ref "R93") (pin "1") (pinfunction "1_1") (pintype "passive"))
      (node (ref "R94") (pin "1") (pinfunction "1_1") (pintype "passive"))
    )
    (net (code "45") (name "Net-(C122-Pad2)") (class "Default")
      (node (ref "C122") (pin "2") (pinfunction "2_2") (pintype "passive"))
      (node (ref "C133") (pin "1") (pinfunction "1_1") (pintype "passive"))
      (node (ref "R131") (pin "1") (pinfunction "1_1") (pintype "passive"))
    )
    (net (code "46") (name "Net-(C129-Pad2)") (class "Default")
      (node (ref "C129") (pin "2") (pinfunction "2_2") (pintype "passive"))
      (node (ref "C146") (pin "1") (pinfunction "1_1") (pintype "passive"))
      (node (ref "R145") (pin "1") (pinfunction "1_1") (pintype "passive"))
    )
    (net (code "47") (name "Net-(C139-Pad1)") (class "Default")
      (node (ref "C139") (pin "1") (pinfunction "1_1") (pintype "passive"))
      (node (ref "R133") (pin "1") (pinfunction "1_1") (pintype "passive"))
      (node (ref "R134") (pin "2") (pinfunction "2_2") (pintype "passive"))
    )
    (net (code "48") (name "Net-(C139-Pad2)") (class "Default")
      (node (ref "C139") (pin "2") (pinfunction "2_2") (pintype "passive"))
      (node (ref "R152") (pin "1") (pinfunction "1_1") (pintype "passive"))
      (node (ref "R153") (pin "2") (pinfunction "2_2") (pintype "passive"))
    )
    (net (code "49") (name "Net-(C140-Pad1)") (class "Default")
      (node (ref "C140") (pin "1") (pinfunction "1_1") (pintype "passive"))
      (node (ref "R135") (pin "2") (pinfunction "2_2") (pintype "passive"))
      (node (ref "R136") (pin "1") (pinfunction "1_1") (pintype "passive"))
    )
    (net (code "50") (name "Net-(C140-Pad2)") (class "Default")
      (node (ref "C140") (pin "2") (pinfunction "2_2") (pintype "passive"))
      (node (ref "R147") (pin "2") (pinfunction "2_2") (pintype "passive"))
      (node (ref "R148") (pin "1") (pinfunction "1_1") (pintype "passive"))
    )
    (net (code "51") (name "Net-(C143-Pad2)") (class "Default")
      (node (ref "C143") (pin "2") (pinfunction "2_2") (pintype "passive"))
      (node (ref "C151") (pin "1") (pinfunction "1_1") (pintype "passive"))
      (node (ref "R150") (pin "1") (pinfunction "1_1") (pintype "passive"))
    )
    (net (code "52") (name "Net-(D2-A)") (class "Default")
      (node (ref "C6") (pin "1") (pinfunction "1_1") (pintype "passive"))
      (node (ref "D2") (pin "1") (pinfunction "A_1") (pintype "passive"))
      (node (ref "D7") (pin "2") (pinfunction "K_2") (pintype "passive"))
      (node (ref "DZ2") (pin "2") (pinfunction "K_2") (pintype "passive"))
    )
    (net (code "53") (name "Net-(D2-K)") (class "Default")
      (node (ref "C4") (pin "1") (pinfunction "1_1") (pintype "passive"))
      (node (ref "D2") (pin "2") (pinfunction "K_2") (pintype "passive"))
      (node (ref "D3") (pin "2") (pinfunction "K_2") (pintype "passive"))
      (node (ref "R6") (pin "1") (pinfunction "1_1") (pintype "passive"))
    )
    (net (code "54") (name "Net-(D3-A)") (class "Default")
      (node (ref "C7") (pin "1") (pinfunction "1_1") (pintype "passive"))
      (node (ref "D3") (pin "1") (pinfunction "A_1") (pintype "passive"))
      (node (ref "D8") (pin "2") (pinfunction "K_2") (pintype "passive"))
      (node (ref "DZ1") (pin "2") (pinfunction "K_2") (pintype "passive"))
    )
    (net (code "55") (name "Net-(D5-A)") (class "Default")
      (node (ref "C10") (pin "1") (pinfunction "1_1") (pintype "passive"))
      (node (ref "C11") (pin "1") (pinfunction "1_1") (pintype "passive"))
      (node (ref "C19") (pin "1") (pinfunction "1_1") (pintype "passive"))
      (node (ref "C2") (pin "1") (pinfunction "1_1") (pintype "passive"))
      (node (ref "D5") (pin "1") (pinfunction "A_1") (pintype "passive"))
      (node (ref "DB2") (pin "1") (pinfunction "K_1") (pintype "passive"))
      (node (ref "R7") (pin "2") (pinfunction "2_2") (pintype "passive"))
      (node (ref "T1") (pin "1") (pinfunction "1_1") (pintype "passive"))
    )
    (net (code "56") (name "Net-(D6-A)") (class "Default")
      (node (ref "C12") (pin "1") (pinfunction "1_1") (pintype "passive"))
      (node (ref "C20") (pin "1") (pinfunction "1_1") (pintype "passive"))
      (node (ref "D6") (pin "1") (pinfunction "A_1") (pintype "passive"))
      (node (ref "L1") (pin "2") (pinfunction "2_2") (pintype "passive"))
      (node (ref "T2") (pin "1") (pinfunction "1_1") (pintype "passive"))
    )
    (net (code "57") (name "Net-(D7-A)") (class "Default")
      (node (ref "D7") (pin "1") (pinfunction "A_1") (pintype "passive"))
      (node (ref "T1") (pin "3") (pinfunction "3_3") (pintype "passive"))
    )
    (net (code "58") (name "Net-(D8-A)") (class "Default")
      (node (ref "D8") (pin "1") (pinfunction "A_1") (pintype "passive"))
      (node (ref "T2") (pin "3") (pinfunction "3_3") (pintype "passive"))
    )
    (net (code "59") (name "Net-(D10-A)") (class "Default")
      (node (ref "D10") (pin "1") (pinfunction "A_1") (pintype "passive"))
      (node (ref "Q1") (pin "2") (pinfunction "D_2") (pintype "passive"))
      (node (ref "RL1") (pin "2") (pinfunction "COIL_A_2") (pintype "passive"))
      (node (ref "RL2") (pin "2") (pinfunction "COIL_A_2") (pintype "passive"))
    )
    (net (code "60") (name "Net-(D10-K)") (class "Default")
      (node (ref "C15") (pin "1") (pinfunction "1_1") (pintype "passive"))
      (node (ref "C17") (pin "2") (pinfunction "2_2") (pintype "passive"))
      (node (ref "D10") (pin "2") (pinfunction "K_2") (pintype "passive"))
      (node (ref "R20") (pin "2") (pinfunction "2_2") (pintype "passive"))
    )
    (net (code "61") (name "Net-(D11-A)") (class "Default")
      (node (ref "D11") (pin "1") (pinfunction "A_1") (pintype "passive"))
      (node (ref "IC4") (pin "4") (pinfunction "Drain_4") (pintype "passive"))
      (node (ref "T1") (pin "2") (pinfunction "2_2") (pintype "passive"))
    )
    (net (code "62") (name "Net-(D11-K)") (class "Default")
      (node (ref "D11") (pin "2") (pinfunction "K_2") (pintype "passive"))
      (node (ref "D5") (pin "2") (pinfunction "K_2") (pintype "passive"))
    )
    (net (code "63") (name "Net-(D12-A)") (class "Default")
      (node (ref "D12") (pin "1") (pinfunction "A_1") (pintype "passive"))
      (node (ref "IC5") (pin "4") (pinfunction "Drain_4") (pintype "passive"))
      (node (ref "T2") (pin "2") (pinfunction "2_2") (pintype "passive"))
    )
    (net (code "64") (name "Net-(D12-K)") (class "Default")
      (node (ref "D12") (pin "2") (pinfunction "K_2") (pintype "passive"))
      (node (ref "D6") (pin "2") (pinfunction "K_2") (pintype "passive"))
    )
    (net (code "65") (name "Net-(D15-K)") (class "Default")
      (node (ref "C29") (pin "2") (pinfunction "2_2") (pintype "passive"))
      (node (ref "D15") (pin "2") (pinfunction "K_2") (pintype "passive"))
      (node (ref "R41") (pin "2") (pinfunction "2_2") (pintype "passive"))
    )
    (net (code "66") (name "Net-(D16-K)") (class "Default")
      (node (ref "C34") (pin "1") (pinfunction "1_1") (pintype "passive"))
      (node (ref "D16") (pin "2") (pinfunction "K_2") (pintype "passive"))
      (node (ref "L5") (pin "1") (pinfunction "1_1") (pintype "passive"))
    )
    (net (code "67") (name "Net-(D17-A1)") (class "Default")
      (node (ref "D17") (pin "1") (pinfunction "A1_1") (pintype "passive"))
      (node (ref "L6") (pin "1") (pinfunction "1_1") (pintype "passive"))
      (node (ref "Q2") (pin "2") (pinfunction "D_2") (pintype "passive"))
      (node (ref "R58") (pin "2") (pinfunction "2_2") (pintype "passive"))
    )
    (net (code "68") (name "Net-(D17-A2)") (class "Default")
      (node (ref "D17") (pin "3") (pinfunction "A2_3") (pintype "passive"))
      (node (ref "L4") (pin "1") (pinfunction "1_1") (pintype "passive"))
      (node (ref "Q3") (pin "2") (pinfunction "D_2") (pintype "passive"))
      (node (ref "R54") (pin "2") (pinfunction "2_2") (pintype "passive"))
    )
    (net (code "69") (name "Net-(D20-A)") (class "Default")
      (node (ref "D20") (pin "1") (pinfunction "A_1") (pintype "passive"))
      (node (ref "R53") (pin "1") (pinfunction "1_1") (pintype "passive"))
      (node (ref "R66") (pin "1") (pinfunction "1_1") (pintype "passive"))
      (node (ref "R75") (pin "2") (pinfunction "2_2") (pintype "passive"))
    )
    (net (code "70") (name "Net-(D20-K)") (class "Default")
      (node (ref "D20") (pin "2") (pinfunction "K_2") (pintype "passive"))
      (node (ref "Q2") (pin "1") (pinfunction "G_1") (pintype "passive"))
      (node (ref "Q6") (pin "3") (pinfunction "E_3") (pintype "passive"))
      (node (ref "R67") (pin "1") (pinfunction "1_1") (pintype "passive"))
    )
    (net (code "71") (name "Net-(D21-A)") (class "Default")
      (node (ref "D21") (pin "1") (pinfunction "A_1") (pintype "passive"))
      (node (ref "R45") (pin "1") (pinfunction "1_1") (pintype "passive"))
      (node (ref "R68") (pin "1") (pinfunction "1_1") (pintype "passive"))
      (node (ref "R76") (pin "2") (pinfunction "2_2") (pintype "passive"))
    )
    (net (code "72") (name "Net-(D21-K)") (class "Default")
      (node (ref "D21") (pin "2") (pinfunction "K_2") (pintype "passive"))
      (node (ref "Q3") (pin "1") (pinfunction "G_1") (pintype "passive"))
      (node (ref "Q7") (pin "3") (pinfunction "E_3") (pintype "passive"))
      (node (ref "R69") (pin "1") (pinfunction "1_1") (pintype "passive"))
    )
    (net (code "73") (name "Net-(D22-A)") (class "Default")
      (node (ref "D22") (pin "1") (pinfunction "A_1") (pintype "passive"))
      (node (ref "Q5") (pin "2") (pinfunction "D_2") (pintype "passive"))
      (node (ref "RL3") (pin "2") (pinfunction "COIL_A_2") (pintype "passive"))
    )
    (net (code "74") (name "Net-(D22-K)") (class "Default")
      (node (ref "C56") (pin "2") (pinfunction "2_2") (pintype "passive"))
      (node (ref "C57") (pin "1") (pinfunction "1_1") (pintype "passive"))
      (node (ref "D22") (pin "2") (pinfunction "K_2") (pintype "passive"))
      (node (ref "R57") (pin "2") (pinfunction "2_2") (pintype "passive"))
      (node (ref "RL3") (pin "1") (pinfunction "COIL_A_1") (pintype "passive"))
    )
    (net (code "75") (name "Net-(D24-A)") (class "Default")
      (node (ref "C51") (pin "1") (pinfunction "1_1") (pintype "passive"))
      (node (ref "C55") (pin "2") (pinfunction "2_2") (pintype "passive"))
      (node (ref "C58") (pin "1") (pinfunction "1_1") (pintype "passive"))
      (node (ref "C61") (pin "1") (pinfunction "1_1") (pintype "passive"))
      (node (ref "D23") (pin "1") (pinfunction "1_1") (pintype "passive"))
      (node (ref "D24") (pin "1") (pinfunction "A_1") (pintype "passive"))
      (node (ref "D25") (pin "1") (pinfunction "1_1") (pintype "passive"))
      (node (ref "DZ4") (pin "1") (pinfunction "A_1") (pintype "passive"))
      (node (ref "IC8") (pin "2") (pinfunction "A_2") (pintype "passive"))
      (node (ref "L7") (pin "1") (pinfunction "1_1") (pintype "passive"))
      (node (ref "R74") (pin "2") (pinfunction "2_2") (pintype "passive"))
      (node (ref "R80") (pin "2") (pinfunction "2_2") (pintype "passive"))
      (node (ref "R88") (pin "2") (pinfunction "2_2") (pintype "passive"))
      (node (ref "SCR1") (pin "1") (pinfunction "K_1") (pintype "passive"))
      (node (ref "TP4") (pin "0") (pinfunction "0_0") (pintype "passive"))
    )
    (net (code "76") (name "Net-(D24-K)") (class "Default")
      (node (ref "C36") (pin "2") (pinfunction "2_2") (pintype "passive"))
      (node (ref "C51") (pin "2") (pinfunction "2_2") (pintype "passive"))
      (node (ref "D18") (pin "2") (pinfunction "2_2") (pintype "passive"))
      (node (ref "D23") (pin "2") (pinfunction "2_2") (pintype "passive"))
      (node (ref "D24") (pin "2") (pinfunction "K_2") (pintype "passive"))
      (node (ref "L7") (pin "4") (pinfunction "4_4") (pintype "passive"))
      (node (ref "R46") (pin "1") (pinfunction "1_1") (pintype "passive"))
      (node (ref "R47") (pin "1") (pinfunction "1_1") (pintype "passive"))
      (node (ref "R48") (pin "1") (pinfunction "1_1") (pintype "passive"))
      (node (ref "SCR1") (pin "3") (pinfunction "A_3") (pintype "passive"))
      (node (ref "TP3") (pin "0") (pinfunction "0_0") (pintype "passive"))
    )
    (net (code "77") (name "Net-(D27-K)") (class "Default")
      (node (ref "C73") (pin "1") (pinfunction "1_1") (pintype "passive"))
      (node (ref "D27") (pin "2") (pinfunction "K_2") (pintype "passive"))
      (node (ref "L10") (pin "1") (pinfunction "1_1") (pintype "passive"))
    )
    (net (code "78") (name "Net-(DB1-A)") (class "Default")
      (node (ref "DB1") (pin "4") (pinfunction "A_4") (pintype "passive"))
      (node (ref "R29") (pin "1") (pinfunction "1_1") (pintype "passive"))
      (node (ref "R32") (pin "2") (pinfunction "2_2") (pintype "passive"))
    )
    (net (code "79") (name "Net-(DB1-AC1)") (class "Default")
      (node (ref "C16") (pin "2") (pinfunction "2_2") (pintype "passive"))
      (node (ref "DB1") (pin "2") (pinfunction "AC1_2") (pintype "passive"))
      (node (ref "RL1") (pin "4") (pinfunction "CT_4") (pintype "passive"))
    )
    (net (code "80") (name "Net-(DB1-AC2)") (class "Default")
      (node (ref "C16") (pin "1") (pinfunction "1_1") (pintype "passive"))
      (node (ref "DB1") (pin "3") (pinfunction "AC2_3") (pintype "passive"))
      (node (ref "RL2") (pin "4") (pinfunction "CT_4") (pintype "passive"))
    )
    (net (code "81") (name "Net-(DB1-K)") (class "Default")
      (node (ref "DB1") (pin "1") (pinfunction "K_1") (pintype "passive"))
      (node (ref "L2") (pin "1") (pinfunction "1_1") (pintype "passive"))
    )
    (net (code "82") (name "Net-(DB2-A)") (class "Default")
      (node (ref "C19") (pin "2") (pinfunction "2_2") (pintype "passive"))
      (node (ref "DB2") (pin "4") (pinfunction "A_4") (pintype "passive"))
      (node (ref "R27") (pin "2") (pinfunction "2_2") (pintype "passive"))
    )
    (net (code "83") (name "Net-(DB2-AC2)") (class "Default")
      (node (ref "DB2") (pin "3") (pinfunction "AC2_3") (pintype "passive"))
      (node (ref "R9") (pin "1") (pinfunction "1_1") (pintype "passive"))
    )
    (net (code "84") (name "Net-(DZ1-A)") (class "Default")
      (node (ref "DZ1") (pin "1") (pinfunction "A_1") (pintype "passive"))
      (node (ref "R11") (pin "2") (pinfunction "2_2") (pintype "passive"))
    )
    (net (code "85") (name "Net-(DZ2-A)") (class "Default")
      (node (ref "DZ2") (pin "1") (pinfunction "A_1") (pintype "passive"))
      (node (ref "R10") (pin "2") (pinfunction "2_2") (pintype "passive"))
    )
    (net (code "86") (name "Net-(DZ3-K)") (class "Default")
      (node (ref "C32") (pin "1") (pinfunction "1_1") (pintype "passive"))
      (node (ref "C33") (pin "2") (pinfunction "2_2") (pintype "passive"))
      (node (ref "DZ3") (pin "2") (pinfunction "K_2") (pintype "passive"))
      (node (ref "IC6") (pin "6") (pinfunction "VDD_6") (pintype "power_in"))
      (node (ref "L5") (pin "2") (pinfunction "2_2") (pintype "passive"))
    )
    (net (code "87") (name "Net-(DZ4-K)") (class "Default")
      (node (ref "C55") (pin "1") (pinfunction "1_1") (pintype "passive"))
      (node (ref "DZ4") (pin "2") (pinfunction "K_2") (pintype "passive"))
      (node (ref "Q4") (pin "3") (pinfunction "E_3") (pintype "passive"))
      (node (ref "R46") (pin "2") (pinfunction "2_2") (pintype "passive"))
      (node (ref "R61") (pin "1") (pinfunction "1_1") (pintype "passive"))
    )
    (net (code "88") (name "Net-(DZ5-K)") (class "Default")
      (node (ref "C71") (pin "1") (pinfunction "1_1") (pintype "passive"))
      (node (ref "C74") (pin "2") (pinfunction "2_2") (pintype "passive"))
      (node (ref "DZ5") (pin "2") (pinfunction "K_2") (pintype "passive"))
      (node (ref "IC11") (pin "16") (pinfunction "VCCL_16") (pintype "power_in"))
      (node (ref "IC11") (pin "17") (pinfunction "VCCH_17") (pintype "power_in"))
      (node (ref "L10") (pin "2") (pinfunction "2_2") (pintype "passive"))
    )
    (net (code "89") (name "Net-(DZ6-A)") (class "Default")
      (node (ref "C80") (pin "2") (pinfunction "2_2") (pintype "passive"))
      (node (ref "C81") (pin "2") (pinfunction "2_2") (pintype "passive"))
      (node (ref "DZ6") (pin "1") (pinfunction "A_1") (pintype "passive"))
      (node (ref "IC11") (pin "25") (pinfunction "VS(U)_25") (pintype "power_in"))
      (node (ref "R101") (pin "1") (pinfunction "1_1") (pintype "passive"))
    )
    (net (code "90") (name "Net-(DZ6-K)") (class "Default")
      (node (ref "C80") (pin "1") (pinfunction "1_1") (pintype "passive"))
      (node (ref "C81") (pin "1") (pinfunction "1_1") (pintype "passive"))
      (node (ref "DZ6") (pin "2") (pinfunction "K_2") (pintype "passive"))
      (node (ref "IC11") (pin "26") (pinfunction "VB(U)_26") (pintype "power_in"))
      (node (ref "R101") (pin "2") (pinfunction "2_2") (pintype "passive"))
    )
    (net (code "91") (name "Net-(DZ7-A)") (class "Default")
      (node (ref "C84") (pin "2") (pinfunction "2_2") (pintype "passive"))
      (node (ref "C85") (pin "2") (pinfunction "2_2") (pintype "passive"))
      (node (ref "DZ7") (pin "1") (pinfunction "A_1") (pintype "passive"))
      (node (ref "IC11") (pin "23") (pinfunction "VS(V)_23") (pintype "power_in"))
      (node (ref "R105") (pin "1") (pinfunction "1_1") (pintype "passive"))
    )
    (net (code "92") (name "Net-(DZ7-K)") (class "Default")
      (node (ref "C84") (pin "1") (pinfunction "1_1") (pintype "passive"))
      (node (ref "C85") (pin "1") (pinfunction "1_1") (pintype "passive"))
      (node (ref "DZ7") (pin "2") (pinfunction "K_2") (pintype "passive"))
      (node (ref "IC11") (pin "24") (pinfunction "VB(V)_24") (pintype "power_in"))
      (node (ref "R105") (pin "2") (pinfunction "2_2") (pintype "passive"))
    )
    (net (code "93") (name "Net-(DZ8-A)") (class "Default")
      (node (ref "C88") (pin "2") (pinfunction "2_2") (pintype "passive"))
      (node (ref "C94") (pin "2") (pinfunction "2_2") (pintype "passive"))
      (node (ref "DZ8") (pin "1") (pinfunction "A_1") (pintype "passive"))
      (node (ref "IC11") (pin "21") (pinfunction "VS(W)_21") (pintype "power_in"))
      (node (ref "R110") (pin "1") (pinfunction "1_1") (pintype "passive"))
    )
    (net (code "94") (name "Net-(DZ8-K)") (class "Default")
      (node (ref "C88") (pin "1") (pinfunction "1_1") (pintype "passive"))
      (node (ref "C94") (pin "1") (pinfunction "1_1") (pintype "passive"))
      (node (ref "DZ8") (pin "2") (pinfunction "K_2") (pintype "passive"))
      (node (ref "IC11") (pin "22") (pinfunction "VB(W)_22") (pintype "power_in"))
      (node (ref "R110") (pin "2") (pinfunction "2_2") (pintype "passive"))
    )
    (net (code "95") (name "Net-(IC1A-VINA+)") (class "Default")
      (node (ref "IC1") (pin "3") (pinfunction "VINA+_3") (pintype "input"))
      (node (ref "R15") (pin "2") (pinfunction "2_2") (pintype "passive"))
      (node (ref "R16") (pin "2") (pinfunction "2_2") (pintype "passive"))
    )
    (net (code "96") (name "Net-(IC1A-VINA-)") (class "Default")
      (node (ref "IC1") (pin "2") (pinfunction "VINA-_2") (pintype "input"))
      (node (ref "R3") (pin "2") (pinfunction "2_2") (pintype "passive"))
      (node (ref "R4") (pin "2") (pinfunction "2_2") (pintype "passive"))
    )
    (net (code "97") (name "Net-(IC1A-VOUTA)") (class "Default")
      (node (ref "IC1") (pin "1") (pinfunction "VOUTA_1") (pintype "output"))
      (node (ref "R4") (pin "1") (pinfunction "1_1") (pintype "passive"))
      (node (ref "R5") (pin "2") (pinfunction "2_2") (pintype "passive"))
    )
    (net (code "98") (name "Net-(IC1B-VINB+)") (class "Default")
      (node (ref "IC1") (pin "5") (pinfunction "VINB+_5") (pintype "input"))
      (node (ref "R25") (pin "2") (pinfunction "2_2") (pintype "passive"))
      (node (ref "R26") (pin "2") (pinfunction "2_2") (pintype "passive"))
    )
    (net (code "99") (name "Net-(IC1B-VINB-)") (class "Default")
      (node (ref "IC1") (pin "6") (pinfunction "VINB-_6") (pintype "input"))
      (node (ref "R33") (pin "2") (pinfunction "2_2") (pintype "passive"))
      (node (ref "R34") (pin "2") (pinfunction "2_2") (pintype "passive"))
    )
    (net (code "100") (name "Net-(IC1B-VOUTB)") (class "Default")
      (node (ref "IC1") (pin "7") (pinfunction "VOUTB_7") (pintype "output"))
      (node (ref "R30") (pin "2") (pinfunction "2_2") (pintype "passive"))
      (node (ref "R34") (pin "1") (pinfunction "1_1") (pintype "passive"))
    )
    (net (code "101") (name "Net-(IC1C-VINC+)") (class "Default")
      (node (ref "IC1") (pin "10") (pinfunction "VINC+_10") (pintype "input"))
      (node (ref "R51") (pin "2") (pinfunction "2_2") (pintype "passive"))
      (node (ref "R52") (pin "2") (pinfunction "2_2") (pintype "passive"))
    )
    (net (code "102") (name "Net-(IC1C-VINC-)") (class "Default")
      (node (ref "IC1") (pin "9") (pinfunction "VINC-_9") (pintype "input"))
      (node (ref "R38") (pin "2") (pinfunction "2_2") (pintype "passive"))
      (node (ref "R39") (pin "2") (pinfunction "2_2") (pintype "passive"))
    )
    (net (code "103") (name "Net-(IC1C-VOUTC)") (class "Default")
      (node (ref "IC1") (pin "8") (pinfunction "VOUTC_8") (pintype "output"))
      (node (ref "R39") (pin "1") (pinfunction "1_1") (pintype "passive"))
      (node (ref "R42") (pin "2") (pinfunction "2_2") (pintype "passive"))
    )
    (net (code "104") (name "Net-(IC1D-VIND+)") (class "Default")
      (node (ref "IC1") (pin "12") (pinfunction "VIND+_12") (pintype "input"))
      (node (ref "R86") (pin "2") (pinfunction "2_2") (pintype "passive"))
      (node (ref "R87") (pin "2") (pinfunction "2_2") (pintype "passive"))
    )
    (net (code "105") (name "Net-(IC1D-VIND-)") (class "Default")
      (node (ref "IC1") (pin "13") (pinfunction "VIND-_13") (pintype "input"))
      (node (ref "R94") (pin "2") (pinfunction "2_2") (pintype "passive"))
      (node (ref "R95") (pin "2") (pinfunction "2_2") (pintype "passive"))
    )
    (net (code "106") (name "Net-(IC1D-VOUTD)") (class "Default")
      (node (ref "IC1") (pin "14") (pinfunction "VOUTD_14") (pintype "output"))
      (node (ref "R91") (pin "2") (pinfunction "2_2") (pintype "passive"))
      (node (ref "R95") (pin "1") (pinfunction "1_1") (pintype "passive"))
    )
    (net (code "107") (name "Net-(IC2-A)") (class "Default")
      (node (ref "IC2") (pin "1") (pinfunction "A_1") (pintype "passive"))
      (node (ref "R10") (pin "1") (pinfunction "1_1") (pintype "passive"))
      (node (ref "R17") (pin "2") (pinfunction "2_2") (pintype "passive"))
    )
    (net (code "108") (name "Net-(IC2-C)") (class "Default")
      (node (ref "IC2") (pin "4") (pinfunction "C_4") (pintype "passive"))
      (node (ref "IC4") (pin "1") (pinfunction "Feedback_1") (pintype "passive"))
    )
    (net (code "109") (name "Net-(IC3-A)") (class "Default")
      (node (ref "IC3") (pin "1") (pinfunction "A_1") (pintype "passive"))
      (node (ref "R11") (pin "1") (pinfunction "1_1") (pintype "passive"))
      (node (ref "R18") (pin "2") (pinfunction "2_2") (pintype "passive"))
    )
    (net (code "110") (name "Net-(IC3-C)") (class "Default")
      (node (ref "IC3") (pin "4") (pinfunction "C_4") (pintype "passive"))
      (node (ref "IC5") (pin "1") (pinfunction "Feedback_1") (pintype "passive"))
    )
    (net (code "111") (name "Net-(IC4-Bypass)") (class "Default")
      (node (ref "C24") (pin "2") (pinfunction "2_2") (pintype "passive"))
      (node (ref "IC4") (pin "2") (pinfunction "Bypass_2") (pintype "passive"))
    )
    (net (code "112") (name "Net-(IC5-Bypass)") (class "Default")
      (node (ref "C25") (pin "2") (pinfunction "2_2") (pintype "passive"))
      (node (ref "IC5") (pin "2") (pinfunction "Bypass_2") (pintype "passive"))
    )
    (net (code "113") (name "Net-(IC6-INA)") (class "Default")
      (node (ref "C28") (pin "2") (pinfunction "2_2") (pintype "passive"))
      (node (ref "IC6") (pin "2") (pinfunction "INA_2") (pintype "input"))
      (node (ref "R35") (pin "2") (pinfunction "2_2") (pintype "passive"))
    )
    (net (code "114") (name "Net-(IC6-INB)") (class "Default")
      (node (ref "C30") (pin "2") (pinfunction "2_2") (pintype "passive"))
      (node (ref "IC6") (pin "4") (pinfunction "INB_4") (pintype "input"))
      (node (ref "R40") (pin "2") (pinfunction "2_2") (pintype "passive"))
    )
    (net (code "115") (name "Net-(IC7A-VINA+)") (class "Default")
      (node (ref "IC7") (pin "3") (pinfunction "VINA+_3") (pintype "input"))
      (node (ref "R64") (pin "2") (pinfunction "2_2") (pintype "passive"))
      (node (ref "R72") (pin "2") (pinfunction "2_2") (pintype "passive"))
    )
    (net (code "116") (name "Net-(IC7A-VINA-)") (class "Default")
      (node (ref "IC7") (pin "2") (pinfunction "VINA-_2") (pintype "input"))
      (node (ref "R83") (pin "2") (pinfunction "2_2") (pintype "passive"))
      (node (ref "R89") (pin "2") (pinfunction "2_2") (pintype "passive"))
    )
    (net (code "117") (name "Net-(IC7A-VOUTA)") (class "Default")
      (node (ref "IC7") (pin "1") (pinfunction "VOUTA_1") (pintype "output"))
      (node (ref "R78") (pin "2") (pinfunction "2_2") (pintype "passive"))
      (node (ref "R89") (pin "1") (pinfunction "1_1") (pintype "passive"))
    )
    (net (code "118") (name "Net-(IC7B-VINB-)") (class "Default")
      (node (ref "C69") (pin "1") (pinfunction "1_1") (pintype "passive"))
      (node (ref "IC7") (pin "6") (pinfunction "VINB-_6") (pintype "input"))
      (node (ref "R98") (pin "1") (pinfunction "1_1") (pintype "passive"))
      (node (ref "R99") (pin "2") (pinfunction "2_2") (pintype "passive"))
    )
    (net (code "119") (name "Net-(IC7B-VOUTB)") (class "Default")
      (node (ref "C69") (pin "2") (pinfunction "2_2") (pintype "passive"))
      (node (ref "IC7") (pin "7") (pinfunction "VOUTB_7") (pintype "output"))
      (node (ref "R103") (pin "2") (pinfunction "2_2") (pintype "passive"))
      (node (ref "R99") (pin "1") (pinfunction "1_1") (pintype "passive"))
    )
    (net (code "120") (name "Net-(IC7C-VINC-)") (class "Default")
      (node (ref "C83") (pin "1") (pinfunction "1_1") (pintype "passive"))
      (node (ref "IC7") (pin "9") (pinfunction "VINC-_9") (pintype "input"))
      (node (ref "R107") (pin "1") (pinfunction "1_1") (pintype "passive"))
      (node (ref "R108") (pin "2") (pinfunction "2_2") (pintype "passive"))
    )
    (net (code "121") (name "Net-(IC7C-VOUTC)") (class "Default")
      (node (ref "C83") (pin "2") (pinfunction "2_2") (pintype "passive"))
      (node (ref "IC7") (pin "8") (pinfunction "VOUTC_8") (pintype "output"))
      (node (ref "R108") (pin "1") (pinfunction "1_1") (pintype "passive"))
      (node (ref "R111") (pin "2") (pinfunction "2_2") (pintype "passive"))
    )
    (net (code "122") (name "Net-(IC7D-VIND+)") (class "Default")
      (node (ref "IC7") (pin "12") (pinfunction "VIND+_12") (pintype "input"))
      (node (ref "R132") (pin "2") (pinfunction "2_2") (pintype "passive"))
      (node (ref "R133") (pin "2") (pinfunction "2_2") (pintype "passive"))
    )
    (net (code "123") (name "Net-(IC7D-VIND-)") (class "Default")
      (node (ref "IC7") (pin "13") (pinfunction "VIND-_13") (pintype "input"))
      (node (ref "R151") (pin "2") (pinfunction "2_2") (pintype "passive"))
      (node (ref "R152") (pin "2") (pinfunction "2_2") (pintype "passive"))
    )
    (net (code "124") (name "Net-(IC7D-VOUTD)") (class "Default")
      (node (ref "IC7") (pin "14") (pinfunction "VOUTD_14") (pintype "output"))
      (node (ref "R126") (pin "1") (pinfunction "1_1") (pintype "passive"))
      (node (ref "R151") (pin "1") (pinfunction "1_1") (pintype "passive"))
    )
    (net (code "125") (name "Net-(IC8-K)") (class "Default")
      (node (ref "IC8") (pin "3") (pinfunction "K_3") (pintype "passive"))
      (node (ref "R61") (pin "2") (pinfunction "2_2") (pintype "passive"))
      (node (ref "R62") (pin "1") (pinfunction "1_1") (pintype "passive"))
    )
    (net (code "126") (name "Net-(IC8-R)") (class "Default")
      (node (ref "C61") (pin "2") (pinfunction "2_2") (pintype "passive"))
      (node (ref "IC8") (pin "1") (pinfunction "R_1") (pintype "passive"))
      (node (ref "R73") (pin "2") (pinfunction "2_2") (pintype "passive"))
      (node (ref "R88") (pin "1") (pinfunction "1_1") (pintype "passive"))
    )
    (net (code "127") (name "Net-(IC9-Input)") (class "Default")
      (node (ref "C65") (pin "1") (pinfunction "1_1") (pintype "passive"))
      (node (ref "C66") (pin "2") (pinfunction "2_2") (pintype "passive"))
      (node (ref "IC9") (pin "1") (pinfunction "Input_1") (pintype "power_in"))
      (node (ref "L8") (pin "1") (pinfunction "1_1") (pintype "passive"))
    )
    (net (code "128") (name "Net-(IC9-Output)") (class "Default")
      (node (ref "C67") (pin "2") (pinfunction "2_2") (pintype "passive"))
      (node (ref "C68") (pin "1") (pinfunction "1_1") (pintype "passive"))
      (node (ref "IC9") (pin "3") (pinfunction "Output_3") (pintype "power_in"))
      (node (ref "R97") (pin "1") (pinfunction "1_1") (pintype "passive"))
    )
    (net (code "129") (name "Net-(IC10-FLTR)") (class "Default")
      (node (ref "C75") (pin "1") (pinfunction "1_1") (pintype "passive"))
      (node (ref "IC10") (pin "6") (pinfunction "FLTR_6") (pintype "passive"))
    )
    (net (code "130") (name "Net-(IC10-IP--Pad3)") (class "Default")
      (node (ref "IC10") (pin "3") (pinfunction "IP-_3") (pintype "passive"))
      (node (ref "IC10") (pin "4") (pinfunction "IP-_4") (pintype "passive"))
      (node (ref "TP5") (pin "0") (pinfunction "0_0") (pintype "passive"))
    )
    (net (code "131") (name "Net-(IC10-VO)") (class "Default")
      (node (ref "IC10") (pin "7") (pinfunction "VO_7") (pintype "passive"))
      (node (ref "R98") (pin "2") (pinfunction "2_2") (pintype "passive"))
    )
    (net (code "132") (name "Net-(IC11-C(SC))") (class "Default")
      (node (ref "C103") (pin "2") (pinfunction "2_2") (pintype "passive"))
      (node (ref "IC11") (pin "10") (pinfunction "C(SC)_10") (pintype "passive"))
      (node (ref "R126") (pin "2") (pinfunction "2_2") (pintype "passive"))
    )
    (net (code "133") (name "Net-(IC11-IN(UH))") (class "Default")
      (node (ref "C95") (pin "1") (pinfunction "1_1") (pintype "passive"))
      (node (ref "IC11") (pin "20") (pinfunction "IN(UH)_20") (pintype "input"))
      (node (ref "R109") (pin "1") (pinfunction "1_1") (pintype "passive"))
    )
    (net (code "134") (name "Net-(IC11-IN(UL))") (class "Default")
      (node (ref "C114") (pin "1") (pinfunction "1_1") (pintype "passive"))
      (node (ref "IC11") (pin "14") (pinfunction "IN(UL)_14") (pintype "input"))
      (node (ref "R120") (pin "1") (pinfunction "1_1") (pintype "passive"))
    )
    (net (code "135") (name "Net-(IC11-IN(VH))") (class "Default")
      (node (ref "C101") (pin "1") (pinfunction "1_1") (pintype "passive"))
      (node (ref "IC11") (pin "19") (pinfunction "IN(VH)_19") (pintype "input"))
      (node (ref "R112") (pin "1") (pinfunction "1_1") (pintype "passive"))
    )
    (net (code "136") (name "Net-(IC11-IN(VL))") (class "Default")
      (node (ref "C123") (pin "1") (pinfunction "1_1") (pintype "passive"))
      (node (ref "IC11") (pin "13") (pinfunction "IN(VL)_13") (pintype "input"))
      (node (ref "R128") (pin "1") (pinfunction "1_1") (pintype "passive"))
    )
    (net (code "137") (name "Net-(IC11-IN(WH))") (class "Default")
      (node (ref "C106") (pin "1") (pinfunction "1_1") (pintype "passive"))
      (node (ref "IC11") (pin "18") (pinfunction "IN(WH)_18") (pintype "input"))
      (node (ref "R114") (pin "1") (pinfunction "1_1") (pintype "passive"))
    )
    (net (code "138") (name "Net-(IC11-IN(WL))") (class "Default")
      (node (ref "C132") (pin "1") (pinfunction "1_1") (pintype "passive"))
      (node (ref "IC11") (pin "12") (pinfunction "IN(WL)_12") (pintype "input"))
      (node (ref "R139") (pin "1") (pinfunction "1_1") (pintype "passive"))
    )
    (net (code "139") (name "Net-(IC11-NU)") (class "Default")
      (node (ref "IC11") (pin "7") (pinfunction "NU_7") (pintype "input"))
      (node (ref "IC11") (pin "8") (pinfunction "NV_8") (pintype "input"))
      (node (ref "IC11") (pin "9") (pinfunction "NW_9") (pintype "input"))
      (node (ref "R134") (pin "1") (pinfunction "1_1") (pintype "passive"))
      (node (ref "R135") (pin "1") (pinfunction "1_1") (pintype "passive"))
      (node (ref "R142") (pin "2") (pinfunction "2_2") (pintype "passive"))
    )
    (net (code "140") (name "Net-(IC11-VFO)") (class "Default")
      (node (ref "C109") (pin "2") (pinfunction "2_2") (pintype "passive"))
      (node (ref "IC11") (pin "11") (pinfunction "VFO_11") (pintype "output"))
      (node (ref "R119") (pin "1") (pinfunction "1_1") (pintype "passive"))
      (node (ref "R123") (pin "1") (pinfunction "1_1") (pintype "passive"))
    )
    (net (code "141") (name "Net-(IC12-Input)") (class "Default")
      (node (ref "C76") (pin "1") (pinfunction "1_1") (pintype "passive"))
      (node (ref "C77") (pin "2") (pinfunction "2_2") (pintype "passive"))
      (node (ref "IC12") (pin "1") (pinfunction "Input_1") (pintype "power_in"))
      (node (ref "L9") (pin "1") (pinfunction "1_1") (pintype "passive"))
    )
    (net (code "142") (name "Net-(IC12-Output)") (class "Default")
      (node (ref "C78") (pin "2") (pinfunction "2_2") (pintype "passive"))
      (node (ref "C79") (pin "1") (pinfunction "1_1") (pintype "passive"))
      (node (ref "IC12") (pin "3") (pinfunction "Output_3") (pintype "power_in"))
      (node (ref "R100") (pin "1") (pinfunction "1_1") (pintype "passive"))
    )
    (net (code "143") (name "Net-(IC13-FLTR)") (class "Default")
      (node (ref "C89") (pin "1") (pinfunction "1_1") (pintype "passive"))
      (node (ref "IC13") (pin "6") (pinfunction "FLTR_6") (pintype "passive"))
    )
    (net (code "144") (name "Net-(IC13-IP--Pad3)") (class "Default")
      (node (ref "IC13") (pin "3") (pinfunction "IP-_3") (pintype "passive"))
      (node (ref "IC13") (pin "4") (pinfunction "IP-_4") (pintype "passive"))
      (node (ref "TP6") (pin "0") (pinfunction "0_0") (pintype "passive"))
    )
    (net (code "145") (name "Net-(IC13-VO)") (class "Default")
      (node (ref "IC13") (pin "7") (pinfunction "VO_7") (pintype "passive"))
      (node (ref "R107") (pin "2") (pinfunction "2_2") (pintype "passive"))
    )
    (net (code "146") (name "Net-(IC14-Input)") (class "Default")
      (node (ref "C90") (pin "1") (pinfunction "1_1") (pintype "passive"))
      (node (ref "C91") (pin "2") (pinfunction "2_2") (pintype "passive"))
      (node (ref "IC14") (pin "1") (pinfunction "Input_1") (pintype "power_in"))
      (node (ref "L11") (pin "1") (pinfunction "1_1") (pintype "passive"))
    )
    (net (code "147") (name "Net-(IC14-Output)") (class "Default")
      (node (ref "C92") (pin "2") (pinfunction "2_2") (pintype "passive"))
      (node (ref "C93") (pin "1") (pinfunction "1_1") (pintype "passive"))
      (node (ref "IC14") (pin "3") (pinfunction "Output_3") (pintype "power_in"))
      (node (ref "R106") (pin "1") (pinfunction "1_1") (pintype "passive"))
    )
    (net (code "148") (name "Net-(IC15-FLTR)") (class "Default")
      (node (ref "C104") (pin "1") (pinfunction "1_1") (pintype "passive"))
      (node (ref "IC15") (pin "6") (pinfunction "FLTR_6") (pintype "passive"))
    )
    (net (code "149") (name "Net-(IC15-IP--Pad3)") (class "Default")
      (node (ref "IC15") (pin "3") (pinfunction "IP-_3") (pintype "passive"))
      (node (ref "IC15") (pin "4") (pinfunction "IP-_4") (pintype "passive"))
      (node (ref "TP7") (pin "0") (pinfunction "0_0") (pintype "passive"))
    )
    (net (code "150") (name "Net-(IC15-VO)") (class "Default")
      (node (ref "IC15") (pin "7") (pinfunction "VO_7") (pintype "passive"))
      (node (ref "R117") (pin "2") (pinfunction "2_2") (pintype "passive"))
    )
    (net (code "151") (name "Net-(IC16B-VINB+)") (class "Default")
      (node (ref "IC16") (pin "5") (pinfunction "VINB+_5") (pintype "input"))
      (node (ref "R136") (pin "2") (pinfunction "2_2") (pintype "passive"))
      (node (ref "R137") (pin "2") (pinfunction "2_2") (pintype "passive"))
    )
    (net (code "152") (name "Net-(IC16B-VINB-)") (class "Default")
      (node (ref "IC16") (pin "6") (pinfunction "VINB-_6") (pintype "input"))
      (node (ref "R148") (pin "2") (pinfunction "2_2") (pintype "passive"))
      (node (ref "R149") (pin "2") (pinfunction "2_2") (pintype "passive"))
    )
    (net (code "153") (name "Net-(IC16B-VOUTB)") (class "Default")
      (node (ref "IC16") (pin "7") (pinfunction "VOUTB_7") (pintype "output"))
      (node (ref "R144") (pin "2") (pinfunction "2_2") (pintype "passive"))
      (node (ref "R149") (pin "1") (pinfunction "1_1") (pintype "passive"))
    )
    (net (code "154") (name "Net-(IC16C-VINC+)") (class "Default")
      (node (ref "C105") (pin "1") (pinfunction "1_1") (pintype "passive"))
      (node (ref "C113") (pin "1") (pinfunction "1_1") (pintype "passive"))
      (node (ref "IC16") (pin "10") (pinfunction "VINC+_10") (pintype "input"))
      (node (ref "R115") (pin "2") (pinfunction "2_2") (pintype "passive"))
      (node (ref "R116") (pin "1") (pinfunction "1_1") (pintype "passive"))
    )
    (net (code "155") (name "Net-(IC16C-VINC-)") (class "Default")
      (node (ref "IC16") (pin "9") (pinfunction "VINC-_9") (pintype "input"))
      (node (ref "R127") (pin "1") (pinfunction "1_1") (pintype "passive"))
    )
    (net (code "156") (name "Net-(IC16D-VIND+)") (class "Default")
      (node (ref "C134") (pin "1") (pinfunction "1_1") (pintype "passive"))
      (node (ref "C148") (pin "1") (pinfunction "1_1") (pintype "passive"))
      (node (ref "IC16") (pin "12") (pinfunction "VIND+_12") (pintype "input"))
      (node (ref "R140") (pin "2") (pinfunction "2_2") (pintype "passive"))
      (node (ref "R141") (pin "1") (pinfunction "1_1") (pintype "passive"))
    )
    (net (code "157") (name "Net-(IC16D-VIND-)") (class "Default")
      (node (ref "IC16") (pin "13") (pinfunction "VIND-_13") (pintype "input"))
      (node (ref "R154") (pin "1") (pinfunction "1_1") (pintype "passive"))
    )
    (net (code "158") (name "Net-(IC17C-VINC+)") (class "Default")
      (node (ref "C115") (pin "1") (pinfunction "1_1") (pintype "passive"))
      (node (ref "C130") (pin "1") (pinfunction "1_1") (pintype "passive"))
      (node (ref "IC17") (pin "10") (pinfunction "VINC+_10") (pintype "input"))
      (node (ref "IC7") (pin "10") (pinfunction "VINC+_10") (pintype "input"))
      (node (ref "IC7") (pin "5") (pinfunction "VINB+_5") (pintype "input"))
      (node (ref "R129") (pin "1") (pinfunction "1_1") (pintype "passive"))
      (node (ref "R130") (pin "2") (pinfunction "2_2") (pintype "passive"))
    )
    (net (code "159") (name "Net-(IC17C-VINC-)") (class "Default")
      (node (ref "C98") (pin "1") (pinfunction "1_1") (pintype "passive"))
      (node (ref "IC17") (pin "9") (pinfunction "VINC-_9") (pintype "input"))
      (node (ref "R117") (pin "1") (pinfunction "1_1") (pintype "passive"))
      (node (ref "R118") (pin "2") (pinfunction "2_2") (pintype "passive"))
    )
    (net (code "160") (name "Net-(IC17C-VOUTC)") (class "Default")
      (node (ref "C98") (pin "2") (pinfunction "2_2") (pintype "passive"))
      (node (ref "IC17") (pin "8") (pinfunction "VOUTC_8") (pintype "output"))
      (node (ref "R118") (pin "1") (pinfunction "1_1") (pintype "passive"))
      (node (ref "R121") (pin "2") (pinfunction "2_2") (pintype "passive"))
    )
    (net (code "161") (name "Net-(IC18-C1+)") (class "Default")
      (node (ref "C124") (pin "1") (pinfunction "1_1") (pintype "passive"))
      (node (ref "IC18") (pin "1") (pinfunction "C1+_1") (pintype "power_in"))
    )
    (net (code "162") (name "Net-(IC18-C1-)") (class "Default")
      (node (ref "C124") (pin "2") (pinfunction "2_2") (pintype "passive"))
      (node (ref "IC18") (pin "3") (pinfunction "C1-_3") (pintype "passive"))
    )
    (net (code "163") (name "Net-(IC18-C2+)") (class "Default")
      (node (ref "C135") (pin "2") (pinfunction "2_2") (pintype "passive"))
      (node (ref "IC18") (pin "4") (pinfunction "C2+_4") (pintype "passive"))
    )
    (net (code "164") (name "Net-(IC18-C2-)") (class "Default")
      (node (ref "C135") (pin "1") (pinfunction "1_1") (pintype "passive"))
      (node (ref "IC18") (pin "5") (pinfunction "C2-_5") (pintype "power_in"))
    )
    (net (code "165") (name "Net-(IC18-V+)") (class "Default")
      (node (ref "C127") (pin "1") (pinfunction "1_1") (pintype "passive"))
      (node (ref "IC18") (pin "2") (pinfunction "V+_2") (pintype "passive"))
    )
    (net (code "166") (name "Net-(IC18-V-)") (class "Default")
      (node (ref "C118") (pin "1") (pinfunction "1_1") (pintype "passive"))
      (node (ref "IC18") (pin "6") (pinfunction "V-_6") (pintype "passive"))
    )
    (net (code "167") (name "Net-(IC18-VCC)") (class "Default")
      (node (ref "C136") (pin "1") (pinfunction "1_1") (pintype "passive"))
      (node (ref "C147") (pin "2") (pinfunction "2_2") (pintype "passive"))
      (node (ref "IC18") (pin "16") (pinfunction "VCC_16") (pintype "power_in"))
      (node (ref "R143") (pin "1") (pinfunction "1_1") (pintype "passive"))
    )
    (net (code "168") (name "Net-(IC19A-PC14-OSC32_IN)") (class "Default")
      (node (ref "C137") (pin "2") (pinfunction "2_2") (pintype "passive"))
      (node (ref "IC19") (pin "3") (pinfunction "PC14-OSC32_IN_3") (pintype "bidirectional"))
      (node (ref "XT2") (pin "2") (pinfunction "2_2") (pintype "passive"))
    )
    (net (code "169") (name "Net-(IC19A-PC15-OSC32_OUT)") (class "Default")
      (node (ref "C138") (pin "2") (pinfunction "2_2") (pintype "passive"))
      (node (ref "IC19") (pin "4") (pinfunction "PC15-OSC32_OUT_4") (pintype "bidirectional"))
      (node (ref "XT2") (pin "1") (pinfunction "1_1") (pintype "passive"))
    )
    (net (code "170") (name "Net-(IC19A-PD0-OSC_IN)") (class "Default")
      (node (ref "C100") (pin "2") (pinfunction "2_2") (pintype "passive"))
      (node (ref "IC19") (pin "5") (pinfunction "PD0-OSC_IN_5") (pintype "bidirectional"))
      (node (ref "XT1") (pin "2") (pinfunction "2_2") (pintype "passive"))
    )
    (net (code "171") (name "Net-(IC19A-PD1-OSC_OUT)") (class "Default")
      (node (ref "C99") (pin "2") (pinfunction "2_2") (pintype "passive"))
      (node (ref "IC19") (pin "6") (pinfunction "PD1-OSC_OUT_6") (pintype "bidirectional"))
      (node (ref "XT1") (pin "1") (pinfunction "1_1") (pintype "passive"))
    )
    (net (code "172") (name "Net-(IC19B-VBAT)") (class "Default")
      (node (ref "B1") (pin "1") (pintype "passive"))
      (node (ref "IC19") (pin "1") (pinfunction "VBAT_1") (pintype "power_in"))
    )
    (net (code "173") (name "Net-(J1-Pad2)") (class "Default")
      (node (ref "J1") (pin "2") (pinfunction "2_2") (pintype "passive"))
      (node (ref "R6") (pin "2") (pinfunction "2_2") (pintype "passive"))
    )
    (net (code "174") (name "Net-(Q1-G)") (class "Default")
      (node (ref "Q1") (pin "1") (pinfunction "G_1") (pintype "passive"))
      (node (ref "R23") (pin "1") (pinfunction "1_1") (pintype "passive"))
    )
    (net (code "175") (name "Net-(Q4-B)") (class "Default")
      (node (ref "Q4") (pin "1") (pinfunction "B_1") (pintype "passive"))
      (node (ref "R62") (pin "2") (pinfunction "2_2") (pintype "passive"))
    )
    (net (code "176") (name "Net-(Q4-C)") (class "Default")
      (node (ref "Q4") (pin "2") (pinfunction "C_2") (pintype "passive"))
      (node (ref "R55") (pin "2") (pinfunction "2_2") (pintype "passive"))
      (node (ref "R74") (pin "1") (pinfunction "1_1") (pintype "passive"))
    )
    (net (code "177") (name "Net-(Q5-G)") (class "Default")
      (node (ref "Q5") (pin "1") (pinfunction "G_1") (pintype "passive"))
      (node (ref "R79") (pin "1") (pinfunction "1_1") (pintype "passive"))
    )
    (net (code "178") (name "Net-(Q6-B)") (class "Default")
      (node (ref "Q6") (pin "1") (pinfunction "B_1") (pintype "passive"))
      (node (ref "R66") (pin "2") (pinfunction "2_2") (pintype "passive"))
    )
    (net (code "179") (name "Net-(Q7-B)") (class "Default")
      (node (ref "Q7") (pin "1") (pinfunction "B_1") (pintype "passive"))
      (node (ref "R68") (pin "2") (pinfunction "2_2") (pintype "passive"))
    )
    (net (code "180") (name "Net-(R1-Pad2)") (class "Default")
      (node (ref "R1") (pin "2") (pinfunction "2_2") (pintype "passive"))
      (node (ref "R2") (pin "1") (pinfunction "1_1") (pintype "passive"))
    )
    (net (code "181") (name "Net-(R2-Pad2)") (class "Default")
      (node (ref "R2") (pin "2") (pinfunction "2_2") (pintype "passive"))
      (node (ref "R3") (pin "1") (pinfunction "1_1") (pintype "passive"))
    )
    (net (code "182") (name "Net-(R12-Pad2)") (class "Default")
      (node (ref "R12") (pin "2") (pinfunction "2_2") (pintype "passive"))
      (node (ref "R19") (pin "1") (pinfunction "1_1") (pintype "passive"))
    )
    (net (code "183") (name "Net-(R13-Pad2)") (class "Default")
      (node (ref "R13") (pin "2") (pinfunction "2_2") (pintype "passive"))
      (node (ref "R14") (pin "1") (pinfunction "1_1") (pintype "passive"))
    )
    (net (code "184") (name "Net-(R14-Pad2)") (class "Default")
      (node (ref "R14") (pin "2") (pinfunction "2_2") (pintype "passive"))
      (node (ref "R15") (pin "1") (pinfunction "1_1") (pintype "passive"))
    )
    (net (code "185") (name "Net-(R19-Pad2)") (class "Default")
      (node (ref "R19") (pin "2") (pinfunction "2_2") (pintype "passive"))
      (node (ref "R21") (pin "1") (pinfunction "1_1") (pintype "passive"))
    )
    (net (code "186") (name "Net-(R21-Pad2)") (class "Default")
      (node (ref "R21") (pin "2") (pinfunction "2_2") (pintype "passive"))
      (node (ref "R22") (pin "1") (pinfunction "1_1") (pintype "passive"))
    )
    (net (code "187") (name "Net-(R36-Pad2)") (class "Default")
      (node (ref "R36") (pin "2") (pinfunction "2_2") (pintype "passive"))
      (node (ref "R37") (pin "1") (pinfunction "1_1") (pintype "passive"))
    )
    (net (code "188") (name "Net-(R37-Pad2)") (class "Default")
      (node (ref "R37") (pin "2") (pinfunction "2_2") (pintype "passive"))
      (node (ref "R38") (pin "1") (pinfunction "1_1") (pintype "passive"))
    )
    (net (code "189") (name "Net-(R44-Pad2)") (class "Default")
      (node (ref "R44") (pin "2") (pinfunction "2_2") (pintype "passive"))
      (node (ref "R56") (pin "1") (pinfunction "1_1") (pintype "passive"))
    )
    (net (code "190") (name "Net-(R47-Pad2)") (class "Default")
      (node (ref "R47") (pin "2") (pinfunction "2_2") (pintype "passive"))
      (node (ref "R60") (pin "1") (pinfunction "1_1") (pintype "passive"))
    )
    (net (code "191") (name "Net-(R48-Pad2)") (class "Default")
      (node (ref "R48") (pin "2") (pinfunction "2_2") (pintype "passive"))
      (node (ref "R59") (pin "1") (pinfunction "1_1") (pintype "passive"))
    )
    (net (code "192") (name "Net-(R49-Pad2)") (class "Default")
      (node (ref "R49") (pin "2") (pinfunction "2_2") (pintype "passive"))
      (node (ref "R50") (pin "1") (pinfunction "1_1") (pintype "passive"))
    )
    (net (code "193") (name "Net-(R50-Pad2)") (class "Default")
      (node (ref "R50") (pin "2") (pinfunction "2_2") (pintype "passive"))
      (node (ref "R51") (pin "1") (pinfunction "1_1") (pintype "passive"))
    )
    (net (code "194") (name "Net-(R56-Pad2)") (class "Default")
      (node (ref "R56") (pin "2") (pinfunction "2_2") (pintype "passive"))
      (node (ref "R63") (pin "1") (pinfunction "1_1") (pintype "passive"))
    )
    (net (code "195") (name "Net-(R59-Pad2)") (class "Default")
      (node (ref "R59") (pin "2") (pinfunction "2_2") (pintype "passive"))
      (node (ref "R65") (pin "1") (pinfunction "1_1") (pintype "passive"))
    )
    (net (code "196") (name "Net-(R60-Pad2)") (class "Default")
      (node (ref "R60") (pin "2") (pinfunction "2_2") (pintype "passive"))
      (node (ref "R73") (pin "1") (pinfunction "1_1") (pintype "passive"))
    )
    (net (code "197") (name "Net-(R63-Pad2)") (class "Default")
      (node (ref "R63") (pin "2") (pinfunction "2_2") (pintype "passive"))
      (node (ref "R77") (pin "1") (pinfunction "1_1") (pintype "passive"))
    )
    (net (code "198") (name "Net-(R65-Pad2)") (class "Default")
      (node (ref "R65") (pin "2") (pinfunction "2_2") (pintype "passive"))
      (node (ref "R80") (pin "1") (pinfunction "1_1") (pintype "passive"))
    )
    (net (code "199") (name "Net-(R70-Pad1)") (class "Default")
      (node (ref "R70") (pin "1") (pinfunction "1_1") (pintype "passive"))
      (node (ref "R71") (pin "2") (pinfunction "2_2") (pintype "passive"))
    )
    (net (code "200") (name "Net-(R71-Pad1)") (class "Default")
      (node (ref "R71") (pin "1") (pinfunction "1_1") (pintype "passive"))
      (node (ref "R72") (pin "1") (pinfunction "1_1") (pintype "passive"))
    )
    (net (code "201") (name "Net-(R81-Pad1)") (class "Default")
      (node (ref "R81") (pin "1") (pinfunction "1_1") (pintype "passive"))
      (node (ref "R82") (pin "2") (pinfunction "2_2") (pintype "passive"))
    )
    (net (code "202") (name "Net-(R82-Pad1)") (class "Default")
      (node (ref "R82") (pin "1") (pinfunction "1_1") (pintype "passive"))
      (node (ref "R83") (pin "1") (pinfunction "1_1") (pintype "passive"))
    )
    (net (code "203") (name "Net-(RL1-COIL_A-Pad1)") (class "Default")
      (node (ref "RL1") (pin "1") (pinfunction "COIL_A_1") (pintype "passive"))
      (node (ref "RL2") (pin "1") (pinfunction "COIL_A_1") (pintype "passive"))
    )
    (net (code "204") (name "Net-(RL3-CT)") (class "Default")
      (node (ref "C29") (pin "1") (pinfunction "1_1") (pintype "passive"))
      (node (ref "C40") (pin "2") (pinfunction "2_2") (pintype "passive"))
      (node (ref "C41") (pin "2") (pinfunction "2_2") (pintype "passive"))
      (node (ref "L4") (pin "2") (pinfunction "2_2") (pintype "passive"))
      (node (ref "L6") (pin "2") (pinfunction "2_2") (pintype "passive"))
      (node (ref "RL3") (pin "4") (pinfunction "CT_4") (pintype "passive"))
    )
    (net (code "205") (name "Net-(SCR1-G)") (class "Default")
      (node (ref "R55") (pin "1") (pinfunction "1_1") (pintype "passive"))
      (node (ref "SCR1") (pin "3") (pinfunction "G_3") (pintype "passive"))
    )
    (net (code "206") (name "PO_1U") (class "Default")
      (node (ref "IC10") (pin "1") (pinfunction "IP+_1") (pintype "passive"))
      (node (ref "IC10") (pin "2") (pinfunction "IP+_2") (pintype "passive"))
      (node (ref "IC11") (pin "4") (pinfunction "U_4") (pintype "output"))
      (node (ref "R131") (pin "2") (pinfunction "2_2") (pintype "passive"))
    )
    (net (code "207") (name "PO_2V") (class "Default")
      (node (ref "IC11") (pin "5") (pinfunction "V_5") (pintype "output"))
      (node (ref "IC13") (pin "1") (pinfunction "IP+_1") (pintype "passive"))
      (node (ref "IC13") (pin "2") (pinfunction "IP+_2") (pintype "passive"))
      (node (ref "R145") (pin "2") (pinfunction "2_2") (pintype "passive"))
    )
    (net (code "208") (name "PO_3W") (class "Default")
      (node (ref "IC11") (pin "6") (pinfunction "W_6") (pintype "output"))
      (node (ref "IC15") (pin "1") (pinfunction "IP+_1") (pintype "passive"))
      (node (ref "IC15") (pin "2") (pinfunction "IP+_2") (pintype "passive"))
      (node (ref "R150") (pin "2") (pinfunction "2_2") (pintype "passive"))
    )
    (net (code "209") (name "PV_L_FTLD") (class "Default")
      (node (ref "C38") (pin "2") (pinfunction "2_2") (pintype "passive"))
      (node (ref "C45") (pin "2") (pinfunction "2_2") (pintype "passive"))
      (node (ref "C46") (pin "1") (pinfunction "1_1") (pintype "passive"))
      (node (ref "C47") (pin "1") (pinfunction "1_1") (pintype "passive"))
      (node (ref "C48") (pin "1") (pinfunction "1_1") (pintype "passive"))
      (node (ref "C49") (pin "1") (pinfunction "1_1") (pintype "passive"))
      (node (ref "C50") (pin "1") (pinfunction "1_1") (pintype "passive"))
      (node (ref "D15") (pin "1") (pinfunction "A_1") (pintype "passive"))
      (node (ref "D19") (pin "2") (pinfunction "2_2") (pintype "passive"))
      (node (ref "F1") (pin "2") (pinfunction "2_2") (pintype "passive"))
      (node (ref "L7") (pin "3") (pinfunction "3_3") (pintype "passive"))
      (node (ref "R41") (pin "1") (pinfunction "1_1") (pintype "passive"))
      (node (ref "R49") (pin "1") (pinfunction "1_1") (pintype "passive"))
      (node (ref "RL3") (pin "3") (pinfunction "NO_3") (pintype "passive"))
    )
    (net (code "210") (name "PV_N_FTLD") (class "Default")
      (node (ref "C21") (pin "2") (pinfunction "2_2") (pintype "passive"))
      (node (ref "C45") (pin "1") (pinfunction "1_1") (pintype "passive"))
      (node (ref "C59") (pin "1") (pinfunction "1_1") (pintype "passive"))
      (node (ref "D26") (pin "1") (pinfunction "1_1") (pintype "passive"))
      (node (ref "L7") (pin "2") (pinfunction "2_2") (pintype "passive"))
      (node (ref "R28") (pin "1") (pinfunction "1_1") (pintype "passive"))
      (node (ref "R36") (pin "1") (pinfunction "1_1") (pintype "passive"))
      (node (ref "R90") (pin "1") (pinfunction "1_1") (pintype "passive"))
      (node (ref "R93") (pin "2") (pinfunction "2_2") (pintype "passive"))
    )
    (net (code "211") (name "PWM_A") (class "Default")
      (node (ref "R35") (pin "1") (pinfunction "1_1") (pintype "passive"))
    )
    (net (code "212") (name "PWM_B") (class "Default")
      (node (ref "R40") (pin "1") (pinfunction "1_1") (pintype "passive"))
    )
    (net (code "213") (name "PWM_UH") (class "Default")
      (node (ref "R109") (pin "2") (pinfunction "2_2") (pintype "passive"))
    )
    (net (code "214") (name "PWM_UL") (class "Default")
      (node (ref "R120") (pin "2") (pinfunction "2_2") (pintype "passive"))
    )
    (net (code "215") (name "PWM_VH") (class "Default")
      (node (ref "R112") (pin "2") (pinfunction "2_2") (pintype "passive"))
    )
    (net (code "216") (name "PWM_VL") (class "Default")
      (node (ref "R128") (pin "2") (pinfunction "2_2") (pintype "passive"))
    )
    (net (code "217") (name "PWM_WH") (class "Default")
      (node (ref "R114") (pin "2") (pinfunction "2_2") (pintype "passive"))
    )
    (net (code "218") (name "PWM_WL") (class "Default")
      (node (ref "R139") (pin "2") (pinfunction "2_2") (pintype "passive"))
    )
    (net (code "219") (name "REF01") (class "Default")
      (node (ref "C108") (pin "2") (pinfunction "2_2") (pintype "passive"))
      (node (ref "IC16") (pin "8") (pinfunction "VOUTC_8") (pintype "output"))
      (node (ref "R127") (pin "2") (pinfunction "2_2") (pintype "passive"))
      (node (ref "R26") (pin "1") (pinfunction "1_1") (pintype "passive"))
      (node (ref "R87") (pin "1") (pinfunction "1_1") (pintype "passive"))
    )
    (net (code "220") (name "REF25") (class "Default")
      (node (ref "C145") (pin "2") (pinfunction "2_2") (pintype "passive"))
      (node (ref "IC16") (pin "14") (pinfunction "VOUTD_14") (pintype "output"))
      (node (ref "R137") (pin "1") (pinfunction "1_1") (pintype "passive"))
      (node (ref "R154") (pin "2") (pinfunction "2_2") (pintype "passive"))
      (node (ref "R16") (pin "1") (pinfunction "1_1") (pintype "passive"))
      (node (ref "R52") (pin "1") (pinfunction "1_1") (pintype "passive"))
    )
    (net (code "221") (name "RL_GD") (class "Default")
      (node (ref "R23") (pin "2") (pinfunction "2_2") (pintype "passive"))
    )
    (net (code "222") (name "RL_PV") (class "Default")
      (node (ref "R79") (pin "2") (pinfunction "2_2") (pintype "passive"))
    )
    (net (code "223") (name "RS1_RX") (class "Default")
      (node (ref "IC18") (pin "13") (pinfunction "R1IN_13") (pintype "input"))
      (node (ref "J5") (pin "1") (pinfunction "1_1") (pintype "passive"))
    )
    (net (code "224") (name "RS1_TX") (class "Default")
      (node (ref "IC18") (pin "14") (pinfunction "T1OUT_14") (pintype "output"))
      (node (ref "J5") (pin "3") (pinfunction "3_3") (pintype "passive"))
    )
    (net (code "225") (name "RS2_RX") (class "Default")
      (node (ref "IC18") (pin "8") (pinfunction "R2IN_8") (pintype "input"))
      (node (ref "J3") (pin "3") (pinfunction "3_3") (pintype "passive"))
    )
    (net (code "226") (name "RS2_TX") (class "Default")
      (node (ref "IC18") (pin "7") (pinfunction "T2OUT_7") (pintype "output"))
      (node (ref "J3") (pin "4") (pinfunction "4_4") (pintype "passive"))
    )
    (net (code "227") (name "U1_RXD") (class "Default")
      (node (ref "IC18") (pin "12") (pinfunction "R1OUT_12") (pintype "output"))
      (node (ref "J4") (pin "3") (pinfunction "3_3") (pintype "passive"))
    )
    (net (code "228") (name "U1_TXD") (class "Default")
      (node (ref "IC18") (pin "11") (pinfunction "T1IN_11") (pintype "input"))
      (node (ref "J4") (pin "1") (pinfunction "1_1") (pintype "passive"))
    )
    (net (code "229") (name "U2_RXD") (class "Default")
      (node (ref "IC18") (pin "9") (pinfunction "R2OUT_9") (pintype "output"))
      (node (ref "J4") (pin "4") (pinfunction "4_4") (pintype "passive"))
    )
    (net (code "230") (name "U2_TXD") (class "Default")
      (node (ref "IC18") (pin "10") (pinfunction "T2IN_10") (pintype "input"))
      (node (ref "J4") (pin "2") (pinfunction "2_2") (pintype "passive"))
    )
    (net (code "231") (name "VBUS_S") (class "Default")
      (node (ref "C60") (pin "1") (pinfunction "1_1") (pintype "passive"))
      (node (ref "R78") (pin "1") (pinfunction "1_1") (pintype "passive"))
      (node (ref "R84") (pin "2") (pinfunction "2_2") (pintype "passive"))
    )
    (net (code "232") (name "VDD") (class "Default")
      (node (ref "C107") (pin "2") (pinfunction "2_2") (pintype "passive"))
      (node (ref "C111") (pin "2") (pinfunction "2_2") (pintype "passive"))
      (node (ref "C117") (pin "2") (pinfunction "2_2") (pintype "passive"))
      (node (ref "C125") (pin "2") (pinfunction "2_2") (pintype "passive"))
      (node (ref "C131") (pin "1") (pinfunction "1_1") (pintype "passive"))
      (node (ref "IC19") (pin "19") (pinfunction "VDD_4_19") (pintype "power_in"))
      (node (ref "IC19") (pin "32") (pinfunction "VDD_1_32") (pintype "power_in"))
      (node (ref "IC19") (pin "48") (pinfunction "VDD_2_48") (pintype "power_in"))
      (node (ref "IC19") (pin "64") (pinfunction "VDD_3_64") (pintype "power_in"))
      (node (ref "R119") (pin "2") (pinfunction "2_2") (pintype "passive"))
      (node (ref "R125") (pin "2") (pinfunction "2_2") (pintype "passive"))
      (node (ref "R143") (pin "2") (pinfunction "2_2") (pintype "passive"))
      (node (ref "R97") (pin "2") (pinfunction "2_2") (pintype "passive"))
    )
    (net (code "233") (name "VDDA") (class "Default")
      (node (ref "C144") (pin "1") (pinfunction "1_1") (pintype "passive"))
      (node (ref "C150") (pin "2") (pinfunction "2_2") (pintype "passive"))
      (node (ref "IC11") (pin "1") (pinfunction "VTH_1") (pintype "power_in"))
      (node (ref "IC19") (pin "13") (pinfunction "VDDA_13") (pintype "power_in"))
      (node (ref "J2") (pin "1") (pinfunction "1_1") (pintype "passive"))
      (node (ref "R100") (pin "2") (pinfunction "2_2") (pintype "passive"))
    )
    (net (code "234") (name "VFO") (class "Default")
      (node (ref "C126") (pin "2") (pinfunction "2_2") (pintype "passive"))
      (node (ref "R123") (pin "2") (pinfunction "2_2") (pintype "passive"))
    )
    (net (code "235") (name "VGD_S") (class "Default")
      (node (ref "C3") (pin "1") (pinfunction "1_1") (pintype "passive"))
      (node (ref "R5") (pin "1") (pinfunction "1_1") (pintype "passive"))
      (node (ref "R8") (pin "2") (pinfunction "2_2") (pintype "passive"))
    )
    (net (code "236") (name "VPV_S") (class "Default")
      (node (ref "C31") (pin "1") (pinfunction "1_1") (pintype "passive"))
      (node (ref "R42") (pin "1") (pinfunction "1_1") (pintype "passive"))
      (node (ref "R43") (pin "2") (pinfunction "2_2") (pintype "passive"))
    )
    (net (code "237") (name "unconnected-(IC19A-PA11-Pad44)") (class "Default")
      (node (ref "IC19") (pin "44") (pinfunction "PA11_44") (pintype "bidirectional"))
    )
    (net (code "238") (name "unconnected-(IC19A-PA13-Pad46)") (class "Default")
      (node (ref "IC19") (pin "46") (pinfunction "PA13_46") (pintype "bidirectional"))
    )
    (net (code "239") (name "unconnected-(IC19A-PA14-Pad49)") (class "Default")
      (node (ref "IC19") (pin "49") (pinfunction "PA14_49") (pintype "bidirectional"))
    )
    (net (code "240") (name "unconnected-(IC19A-PA15-Pad50)") (class "Default")
      (node (ref "IC19") (pin "50") (pinfunction "PA15_50") (pintype "bidirectional"))
    )
    (net (code "241") (name "unconnected-(IC19A-PB2-Pad28)") (class "Default")
      (node (ref "IC19") (pin "28") (pinfunction "PB2_28") (pintype "bidirectional"))
    )
    (net (code "242") (name "unconnected-(IC19A-PB3-Pad55)") (class "Default")
      (node (ref "IC19") (pin "55") (pinfunction "PB3_55") (pintype "bidirectional"))
    )
    (net (code "243") (name "unconnected-(IC19A-PB4-Pad56)") (class "Default")
      (node (ref "IC19") (pin "56") (pinfunction "PB4_56") (pintype "bidirectional"))
    )
    (net (code "244") (name "unconnected-(IC19A-PB5-Pad57)") (class "Default")
      (node (ref "IC19") (pin "57") (pinfunction "PB5_57") (pintype "bidirectional"))
    )
    (net (code "245") (name "unconnected-(IC19A-PB6-Pad58)") (class "Default")
      (node (ref "IC19") (pin "58") (pinfunction "PB6_58") (pintype "bidirectional"))
    )
    (net (code "246") (name "unconnected-(IC19A-PB7-Pad59)") (class "Default")
      (node (ref "IC19") (pin "59") (pinfunction "PB7_59") (pintype "bidirectional"))
    )
    (net (code "247") (name "unconnected-(IC19A-PB8-Pad61)") (class "Default")
      (node (ref "IC19") (pin "61") (pinfunction "PB8_61") (pintype "bidirectional"))
    )
    (net (code "248") (name "unconnected-(IC19A-PB9-Pad62)") (class "Default")
      (node (ref "IC19") (pin "62") (pinfunction "PB9_62") (pintype "bidirectional"))
    )
    (net (code "249") (name "unconnected-(IC19A-PC6-Pad37)") (class "Default")
      (node (ref "IC19") (pin "37") (pinfunction "PC6_37") (pintype "bidirectional"))
    )
    (net (code "250") (name "unconnected-(IC19A-PC7-Pad38)") (class "Default")
      (node (ref "IC19") (pin "38") (pinfunction "PC7_38") (pintype "bidirectional"))
    )
    (net (code "251") (name "unconnected-(IC19A-PC8-Pad39)") (class "Default")
      (node (ref "IC19") (pin "39") (pinfunction "PC8_39") (pintype "bidirectional"))
    )
    (net (code "252") (name "unconnected-(IC19A-PC9-Pad40)") (class "Default")
      (node (ref "IC19") (pin "40") (pinfunction "PC9_40") (pintype "bidirectional"))
    )
    (net (code "253") (name "unconnected-(IC19A-PC10-Pad51)") (class "Default")
      (node (ref "IC19") (pin "51") (pinfunction "PC10_51") (pintype "bidirectional"))
    )
    (net (code "254") (name "unconnected-(IC19A-PC11-Pad52)") (class "Default")
      (node (ref "IC19") (pin "52") (pinfunction "PC11_52") (pintype "bidirectional"))
    )
    (net (code "255") (name "unconnected-(IC19A-PC12-Pad53)") (class "Default")
      (node (ref "IC19") (pin "53") (pinfunction "PC12_53") (pintype "bidirectional"))
    )
    (net (code "256") (name "unconnected-(IC19A-PC13-TAMPER-RTC-Pad2)") (class "Default")
      (node (ref "IC19") (pin "2") (pinfunction "PC13-TAMPER-RTC_2") (pintype "bidirectional"))
    )
    (net (code "257") (name "unconnected-(IC19A-PD2-Pad54)") (class "Default")
      (node (ref "IC19") (pin "54") (pinfunction "PD2_54") (pintype "bidirectional"))
    )
  )
)
